# controller.net
KiCad netlist of a schematic drawn in EAGLE
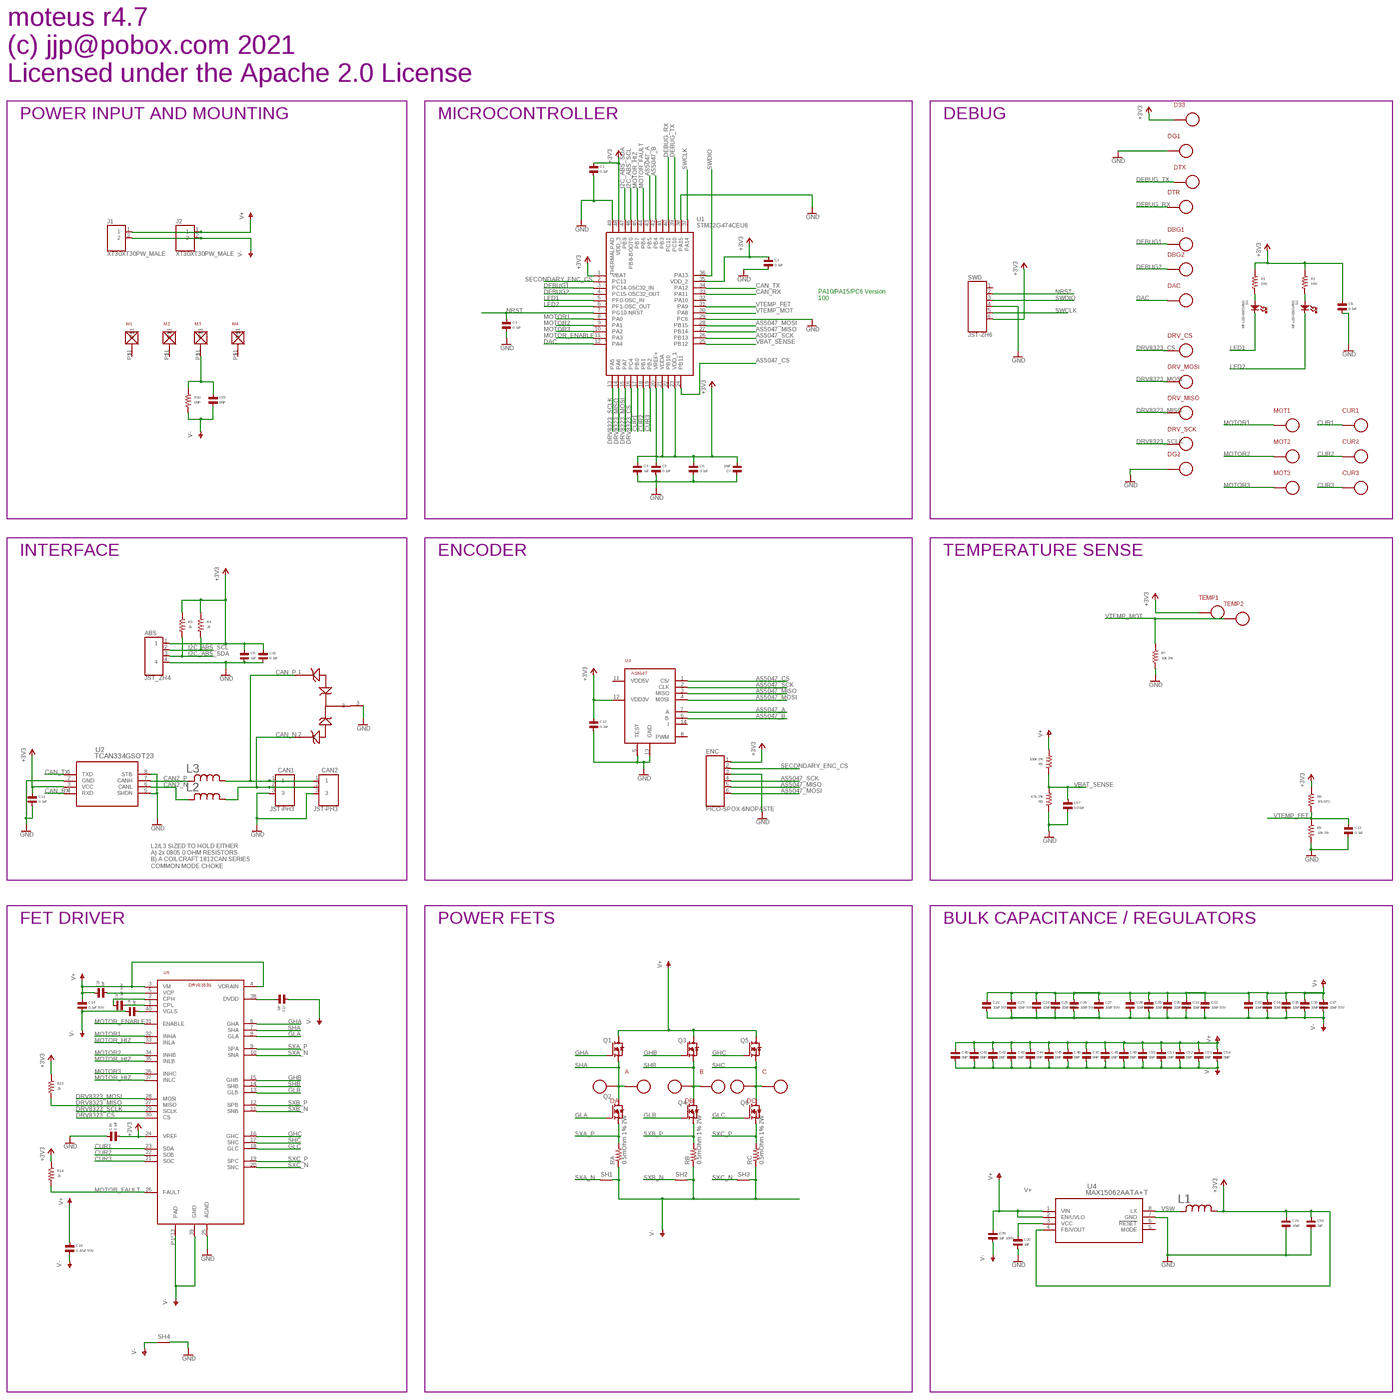
[diagram p0: schematic, sheet 1, overview]
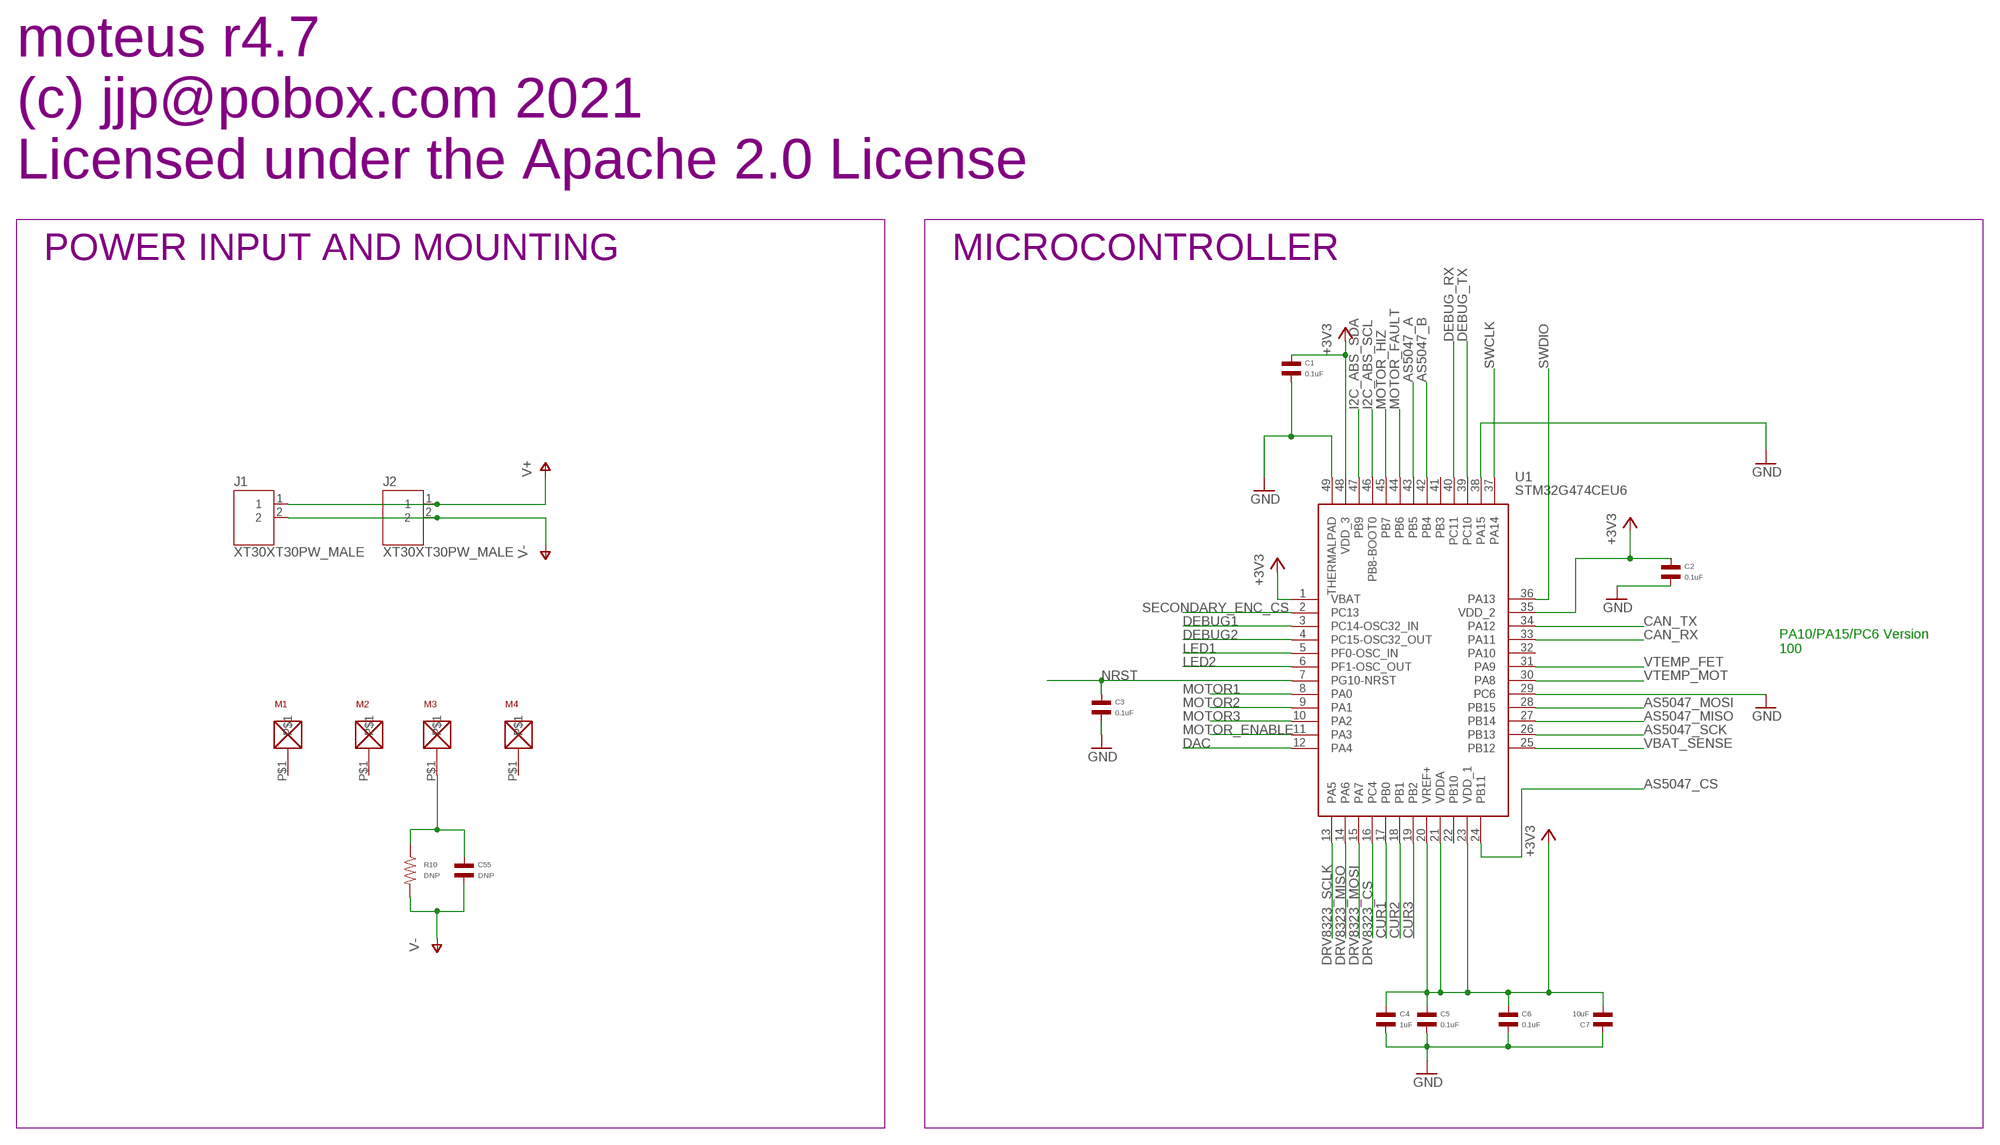
[diagram p1: schematic, sheet 1, part 1 of 4]
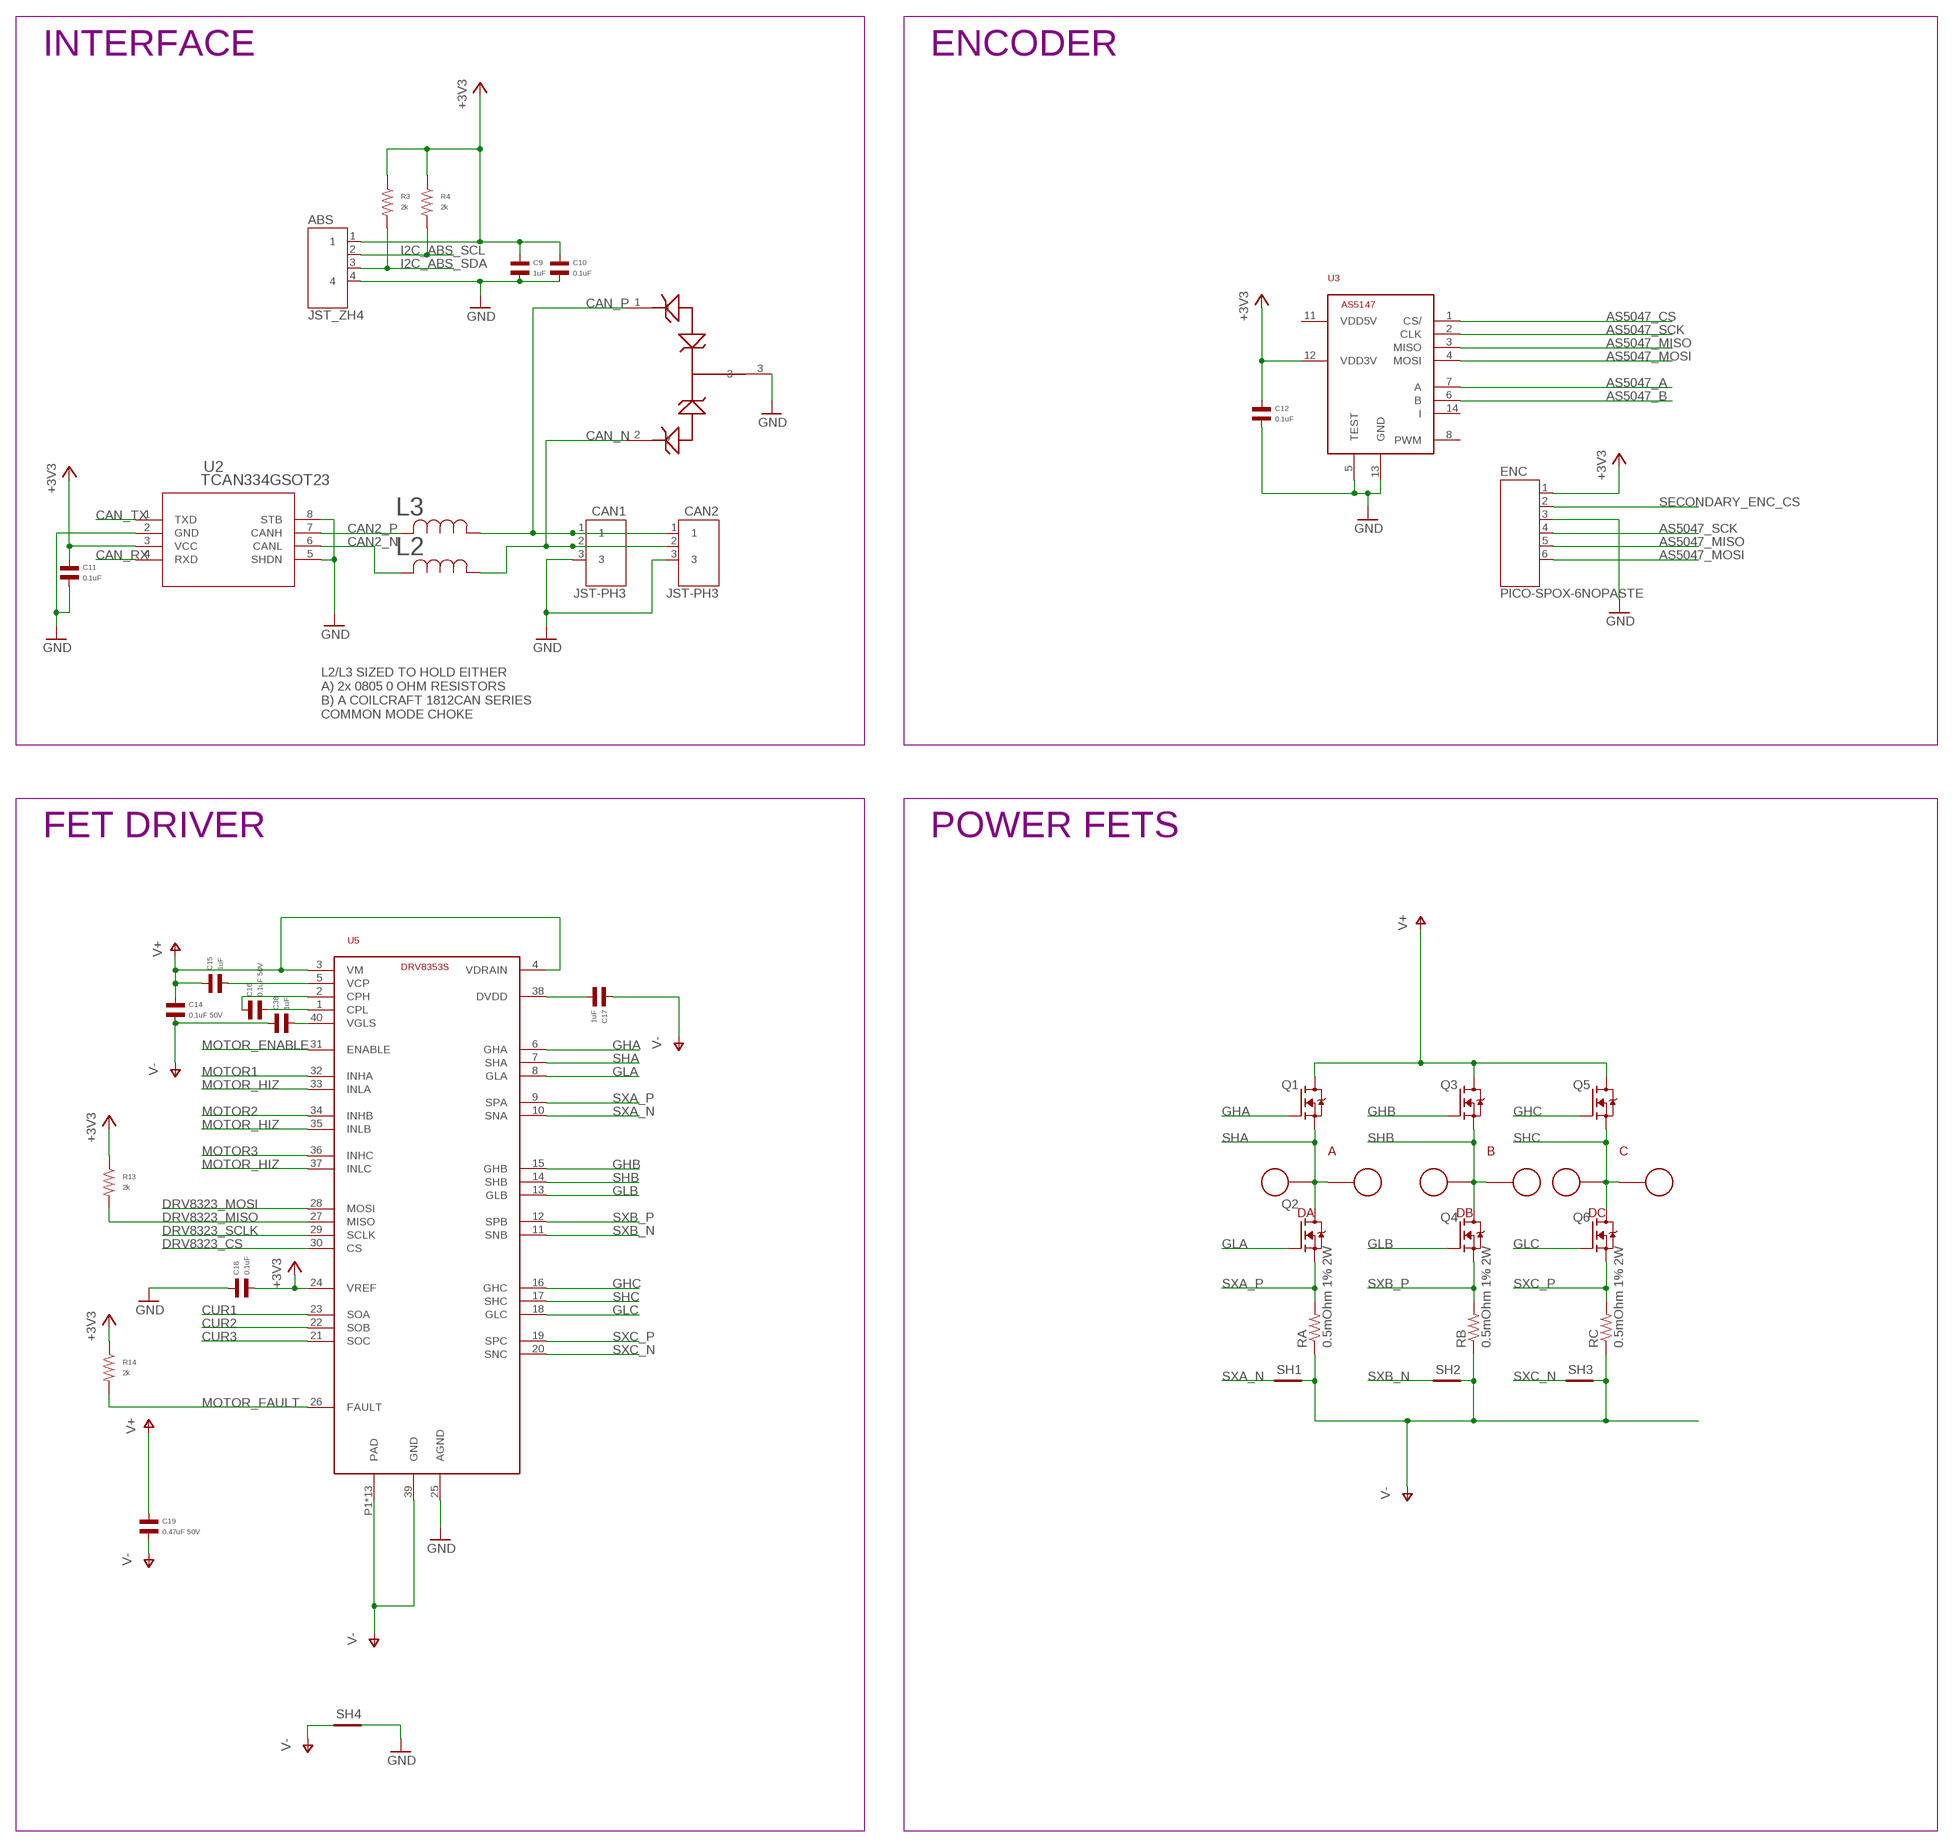
[diagram p2: schematic, sheet 1, part 2 of 4]
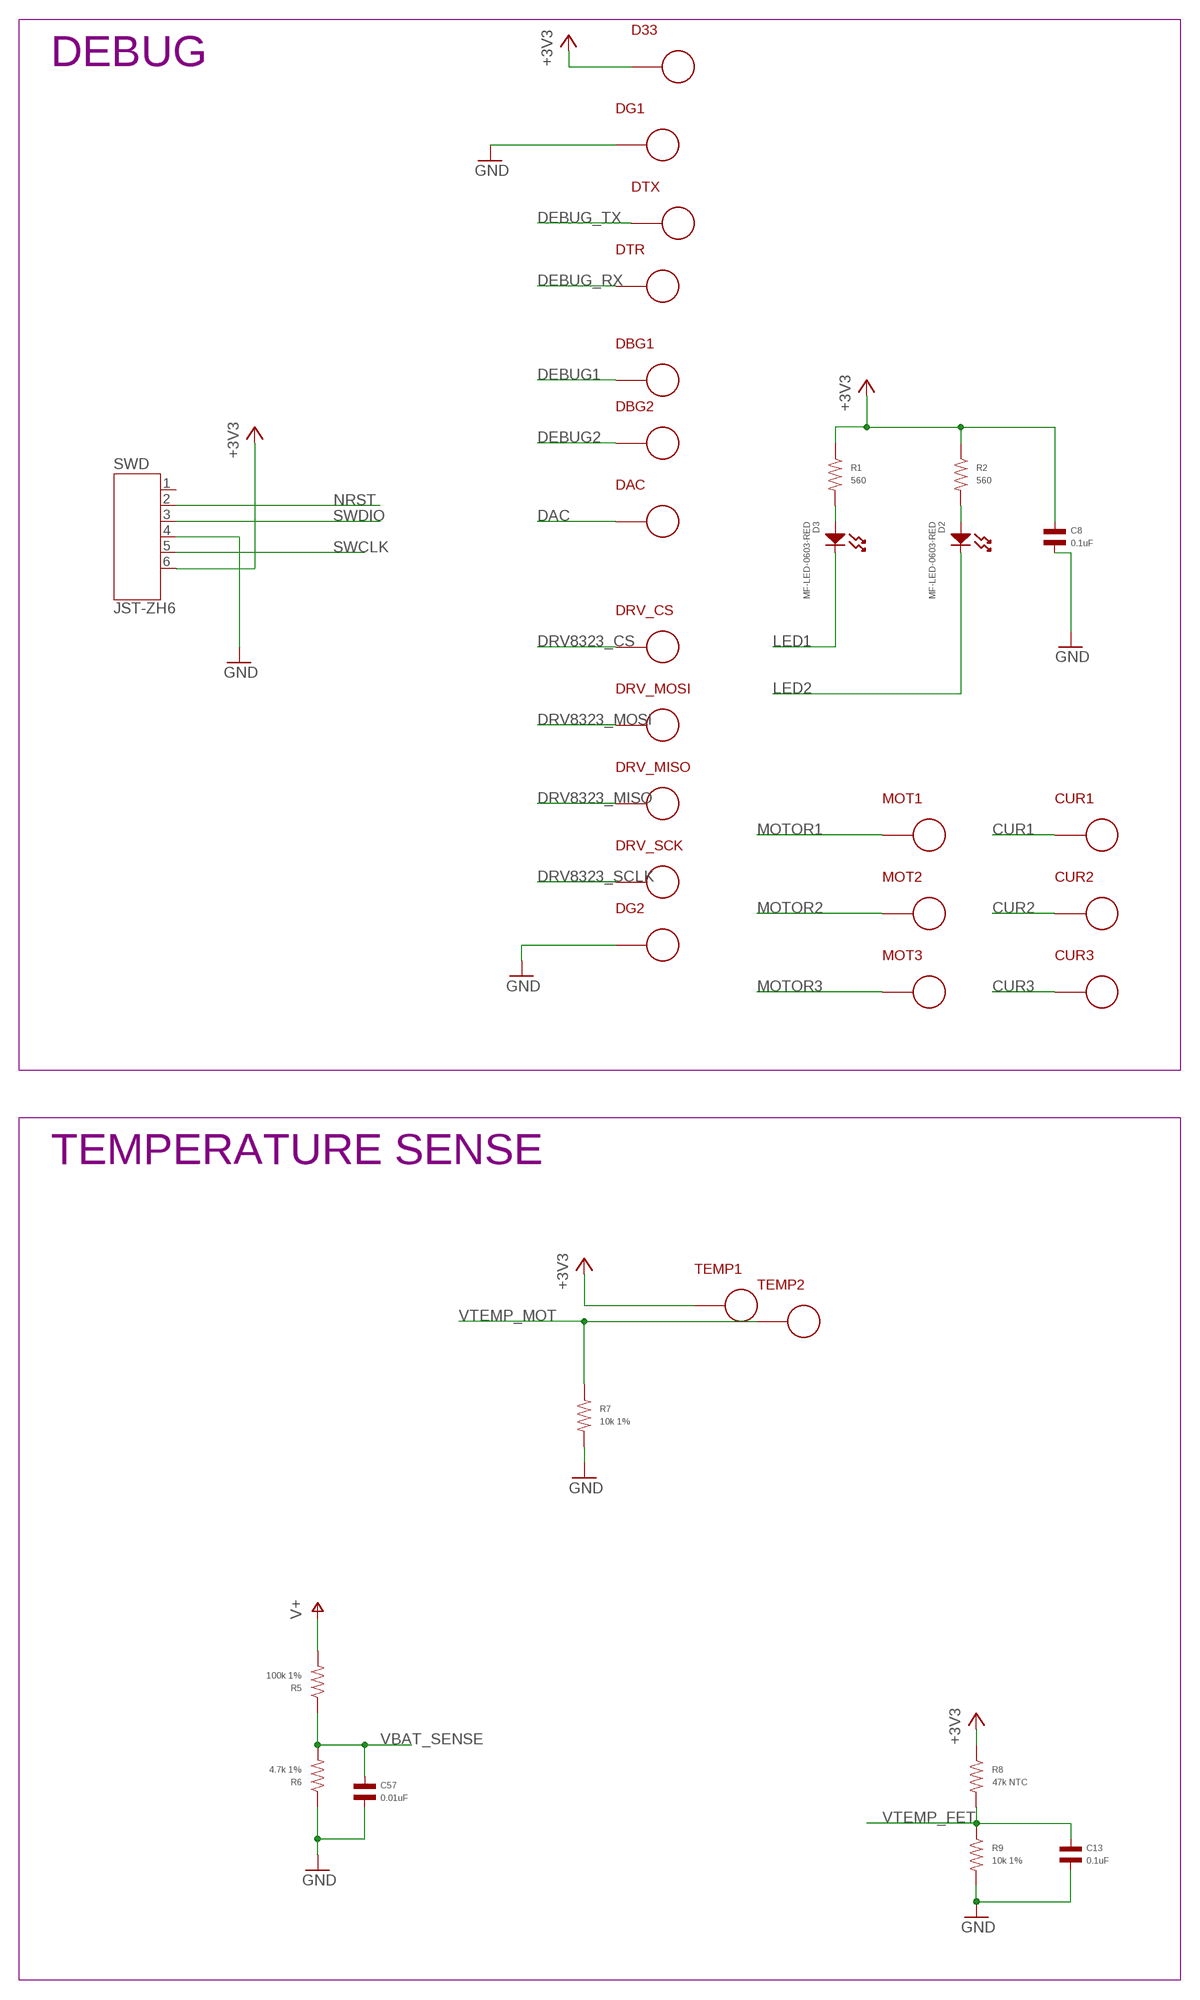
[diagram p3: schematic, sheet 1, part 3 of 4]
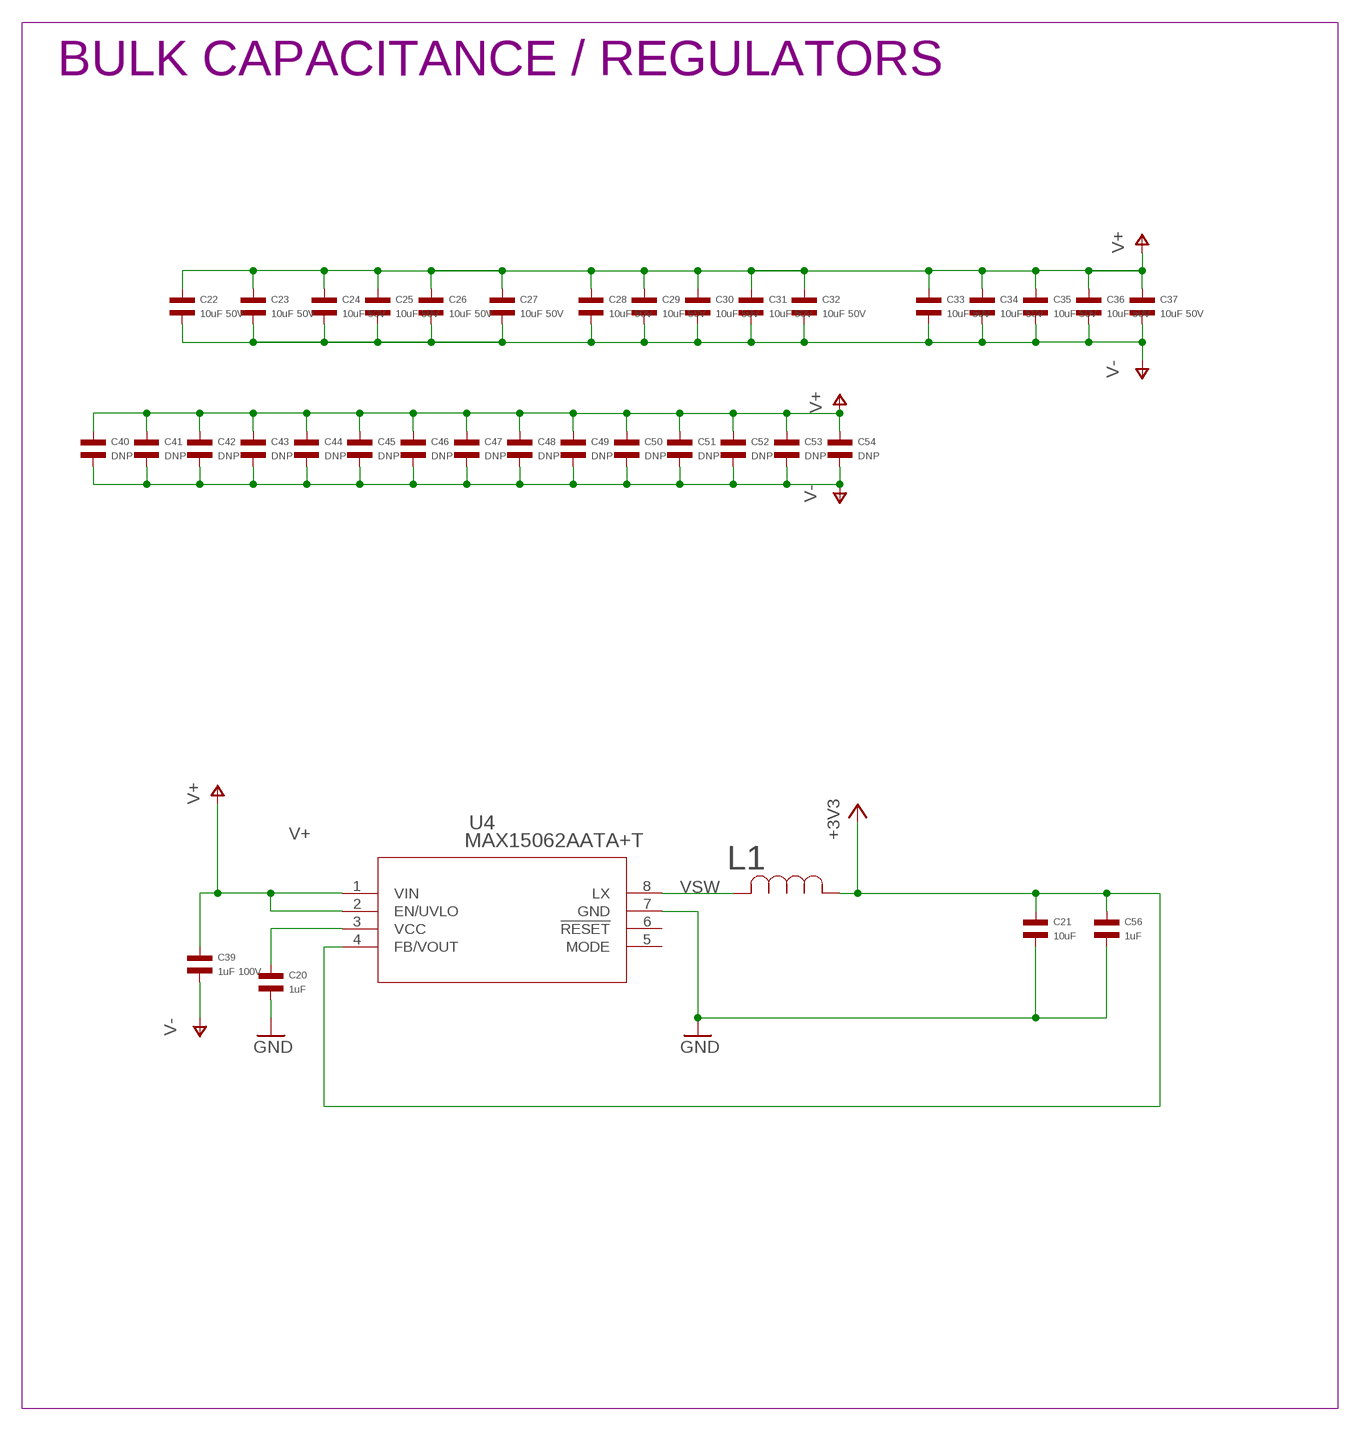
[diagram p4: schematic, sheet 1, part 4 of 4]

(export (version "E")
  (design (tool "Eeschema 10.0.6"))
  (components
    (comp (ref "A")
      (value "PAD16AWG_PAD")
      (footprint "eagle-import:16AWG_PAD")
      (libsource (lib "eagle-import") (part "PAD16AWG_PAD"))
    )
    (comp (ref "ABS")
      (value "JST_ZH4")
      (footprint "eagle-import:JST_S4B-ZR-SM4A-TF(LF)(SN)")
      (fields (field (name "MF") "JST") (field (name "MPN") "S4B-ZR-SM4A-TF(LF)(SN)"))
      (libsource (lib "eagle-import") (part "JST_ZH4"))
    )
    (comp (ref "B")
      (value "PAD16AWG_PAD")
      (footprint "eagle-import:16AWG_PAD")
      (libsource (lib "eagle-import") (part "PAD16AWG_PAD"))
    )
    (comp (ref "C")
      (value "PAD16AWG_PAD")
      (footprint "eagle-import:16AWG_PAD")
      (libsource (lib "eagle-import") (part "PAD16AWG_PAD"))
    )
    (comp (ref "C1")
      (value "0.1uF")
      (footprint "eagle-import:C0402")
      (fields (field (name "HOUSEPART") "YES") (field (name "MPN") "MF-CAP-0402-0.1uF"))
      (libsource (lib "eagle-import") (part "mfpassives_CAPACITOR_NP_0402"))
    )
    (comp (ref "C2")
      (value "0.1uF")
      (footprint "eagle-import:C0402")
      (fields (field (name "HOUSEPART") "YES") (field (name "MPN") "MF-CAP-0402-0.1uF"))
      (libsource (lib "eagle-import") (part "mfpassives_CAPACITOR_NP_0402"))
    )
    (comp (ref "C3")
      (value "0.1uF")
      (footprint "eagle-import:C0402")
      (fields (field (name "HOUSEPART") "YES") (field (name "MPN") "MF-CAP-0402-0.1uF"))
      (libsource (lib "eagle-import") (part "mfpassives_CAPACITOR_NP_0402"))
    )
    (comp (ref "C4")
      (value "1uF")
      (footprint "eagle-import:C0402")
      (fields (field (name "HOUSEPART") "YES") (field (name "MPN") "MF-CAP-0402-1uF"))
      (libsource (lib "eagle-import") (part "mfpassives_CAPACITOR_NP_0402"))
    )
    (comp (ref "C5")
      (value "0.1uF")
      (footprint "eagle-import:C0402")
      (fields (field (name "HOUSEPART") "YES") (field (name "MPN") "MF-CAP-0402-0.1uF"))
      (libsource (lib "eagle-import") (part "mfpassives_CAPACITOR_NP_0402"))
    )
    (comp (ref "C6")
      (value "0.1uF")
      (footprint "eagle-import:C0402")
      (fields (field (name "HOUSEPART") "YES") (field (name "MPN") "MF-CAP-0402-0.1uF"))
      (libsource (lib "eagle-import") (part "mfpassives_CAPACITOR_NP_0402"))
    )
    (comp (ref "C7")
      (value "10uF")
      (footprint "eagle-import:C1206")
      (fields (field (name "HOUSEPART") "YES") (field (name "MPN") "MF-CAP-1206-10uF"))
      (libsource (lib "eagle-import") (part "mfpassives_CAPACITOR_NP_1206"))
    )
    (comp (ref "C8")
      (value "0.1uF")
      (footprint "eagle-import:C0402")
      (fields (field (name "HOUSEPART") "YES") (field (name "MPN") "MF-CAP-0402-0.1uF"))
      (libsource (lib "eagle-import") (part "mfpassives_CAPACITOR_NP_0402"))
    )
    (comp (ref "C9")
      (value "1uF")
      (footprint "eagle-import:C0402")
      (fields (field (name "HOUSEPART") "YES") (field (name "MPN") "MF-CAP-0402-1uF"))
      (libsource (lib "eagle-import") (part "mfpassives_CAPACITOR_NP_0402"))
    )
    (comp (ref "C10")
      (value "0.1uF")
      (footprint "eagle-import:C0402")
      (fields (field (name "HOUSEPART") "YES") (field (name "MPN") "MF-CAP-0402-0.1uF"))
      (libsource (lib "eagle-import") (part "mfpassives_CAPACITOR_NP_0402"))
    )
    (comp (ref "C11")
      (value "0.1uF")
      (footprint "eagle-import:C0402")
      (fields (field (name "HOUSEPART") "YES") (field (name "MPN") "MF-CAP-0402-0.1uF"))
      (libsource (lib "eagle-import") (part "mfpassives_CAPACITOR_NP_0402"))
    )
    (comp (ref "C12")
      (value "0.1uF")
      (footprint "eagle-import:C0402")
      (fields (field (name "HOUSEPART") "YES") (field (name "MPN") "MF-CAP-0402-0.1uF"))
      (libsource (lib "eagle-import") (part "mfpassives_CAPACITOR_NP_0402"))
    )
    (comp (ref "C13")
      (value "0.1uF")
      (footprint "eagle-import:C0402")
      (fields (field (name "HOUSEPART") "YES") (field (name "MPN") "MF-CAP-0402-0.1uF"))
      (libsource (lib "eagle-import") (part "mfpassives_CAPACITOR_NP_0402"))
    )
    (comp (ref "C14")
      (value "0.1uF 50V")
      (footprint "eagle-import:C0402")
      (fields (field (name "MF") "TDK") (field (name "MPN") "CGA2B3X7R1H104K050BB"))
      (libsource (lib "eagle-import") (part "mfpassives_CAPACITOR_NP_0402"))
    )
    (comp (ref "C15")
      (value "1uF")
      (footprint "eagle-import:C0402")
      (fields (field (name "HOUSEPART") "YES") (field (name "MPN") "MF-CAP-0402-1uF"))
      (libsource (lib "eagle-import") (part "mfpassives_CAPACITOR_NP_0402"))
    )
    (comp (ref "C16")
      (value "0.1uF 50V")
      (footprint "eagle-import:C0402")
      (fields (field (name "MF") "TDK") (field (name "MPN") "CGA2B3X7R1H104K050BB"))
      (libsource (lib "eagle-import") (part "mfpassives_CAPACITOR_NP_0402"))
    )
    (comp (ref "C17")
      (value "1uF")
      (footprint "eagle-import:C0402")
      (fields (field (name "HOUSEPART") "YES") (field (name "MPN") "MF-CAP-0402-1uF"))
      (libsource (lib "eagle-import") (part "mfpassives_CAPACITOR_NP_0402"))
    )
    (comp (ref "C18")
      (value "0.1uF")
      (footprint "eagle-import:C0402")
      (fields (field (name "HOUSEPART") "YES") (field (name "MPN") "MF-CAP-0402-0.1uF"))
      (libsource (lib "eagle-import") (part "mfpassives_CAPACITOR_NP_0402"))
    )
    (comp (ref "C19")
      (value "0.47uF 50V")
      (footprint "eagle-import:C0402")
      (fields (field (name "MF") "Murata") (field (name "MPN") "GRM155R61H474KE11D"))
      (libsource (lib "eagle-import") (part "mfpassives_CAPACITOR_NP_0402"))
    )
    (comp (ref "C20")
      (value "1uF")
      (footprint "eagle-import:C0603")
      (fields (field (name "HOUSEPART") "1") (field (name "MPN") "MF-CAP-0603-1uF"))
      (libsource (lib "eagle-import") (part "mfpassives_CAPACITOR_NP_0603"))
    )
    (comp (ref "C21")
      (value "10uF")
      (footprint "eagle-import:C1206")
      (fields (field (name "HOUSEPART") "1") (field (name "MPN") "MF-CAP-1206-10uF"))
      (libsource (lib "eagle-import") (part "mfpassives_CAPACITOR_NP_1206"))
    )
    (comp (ref "C22")
      (value "10uF 50V")
      (footprint "eagle-import:C1206")
      (fields (field (name "MF") "TDK") (field (name "MPN") "C3216X7R1H106K160AE"))
      (libsource (lib "eagle-import") (part "mfpassives_CAPACITOR_NP_1206"))
    )
    (comp (ref "C23")
      (value "10uF 50V")
      (footprint "eagle-import:C1206")
      (fields (field (name "MF") "TDK") (field (name "MPN") "C3216X7R1H106K160AE"))
      (libsource (lib "eagle-import") (part "mfpassives_CAPACITOR_NP_1206"))
    )
    (comp (ref "C24")
      (value "10uF 50V")
      (footprint "eagle-import:C1206")
      (fields (field (name "MF") "TDK") (field (name "MPN") "C3216X7R1H106K160AE"))
      (libsource (lib "eagle-import") (part "mfpassives_CAPACITOR_NP_1206"))
    )
    (comp (ref "C25")
      (value "10uF 50V")
      (footprint "eagle-import:C1206")
      (fields (field (name "MF") "TDK") (field (name "MPN") "C3216X7R1H106K160AE"))
      (libsource (lib "eagle-import") (part "mfpassives_CAPACITOR_NP_1206"))
    )
    (comp (ref "C26")
      (value "10uF 50V")
      (footprint "eagle-import:C1206")
      (fields (field (name "MF") "TDK") (field (name "MPN") "C3216X7R1H106K160AE"))
      (libsource (lib "eagle-import") (part "mfpassives_CAPACITOR_NP_1206"))
    )
    (comp (ref "C27")
      (value "10uF 50V")
      (footprint "eagle-import:C1206")
      (fields (field (name "MF") "TDK") (field (name "MPN") "C3216X7R1H106K160AE"))
      (libsource (lib "eagle-import") (part "mfpassives_CAPACITOR_NP_1206"))
    )
    (comp (ref "C28")
      (value "10uF 50V")
      (footprint "eagle-import:C1206")
      (fields (field (name "MF") "TDK") (field (name "MPN") "C3216X7R1H106K160AE"))
      (libsource (lib "eagle-import") (part "mfpassives_CAPACITOR_NP_1206"))
    )
    (comp (ref "C29")
      (value "10uF 50V")
      (footprint "eagle-import:C1206")
      (fields (field (name "MF") "TDK") (field (name "MPN") "C3216X7R1H106K160AE"))
      (libsource (lib "eagle-import") (part "mfpassives_CAPACITOR_NP_1206"))
    )
    (comp (ref "C30")
      (value "10uF 50V")
      (footprint "eagle-import:C1206")
      (fields (field (name "MF") "TDK") (field (name "MPN") "C3216X7R1H106K160AE"))
      (libsource (lib "eagle-import") (part "mfpassives_CAPACITOR_NP_1206"))
    )
    (comp (ref "C31")
      (value "10uF 50V")
      (footprint "eagle-import:C1206")
      (fields (field (name "MF") "TDK") (field (name "MPN") "C3216X7R1H106K160AE"))
      (libsource (lib "eagle-import") (part "mfpassives_CAPACITOR_NP_1206"))
    )
    (comp (ref "C32")
      (value "10uF 50V")
      (footprint "eagle-import:C1206")
      (fields (field (name "MF") "TDK") (field (name "MPN") "C3216X7R1H106K160AE"))
      (libsource (lib "eagle-import") (part "mfpassives_CAPACITOR_NP_1206"))
    )
    (comp (ref "C33")
      (value "10uF 50V")
      (footprint "eagle-import:C1206")
      (fields (field (name "MF") "TDK") (field (name "MPN") "C3216X7R1H106K160AE"))
      (libsource (lib "eagle-import") (part "mfpassives_CAPACITOR_NP_1206"))
    )
    (comp (ref "C34")
      (value "10uF 50V")
      (footprint "eagle-import:C1206")
      (fields (field (name "MF") "TDK") (field (name "MPN") "C3216X7R1H106K160AE"))
      (libsource (lib "eagle-import") (part "mfpassives_CAPACITOR_NP_1206"))
    )
    (comp (ref "C35")
      (value "10uF 50V")
      (footprint "eagle-import:C1206")
      (fields (field (name "MF") "TDK") (field (name "MPN") "C3216X7R1H106K160AE"))
      (libsource (lib "eagle-import") (part "mfpassives_CAPACITOR_NP_1206"))
    )
    (comp (ref "C36")
      (value "10uF 50V")
      (footprint "eagle-import:C1206")
      (fields (field (name "MF") "TDK") (field (name "MPN") "C3216X7R1H106K160AE"))
      (libsource (lib "eagle-import") (part "mfpassives_CAPACITOR_NP_1206"))
    )
    (comp (ref "C37")
      (value "10uF 50V")
      (footprint "eagle-import:C1206")
      (fields (field (name "MF") "TDK") (field (name "MPN") "C3216X7R1H106K160AE"))
      (libsource (lib "eagle-import") (part "mfpassives_CAPACITOR_NP_1206"))
    )
    (comp (ref "C38")
      (value "1uF")
      (footprint "eagle-import:C0402")
      (fields (field (name "HOUSEPART") "YES") (field (name "MPN") "MF-CAP-0402-1uF"))
      (libsource (lib "eagle-import") (part "mfpassives_CAPACITOR_NP_0402"))
    )
    (comp (ref "C39")
      (value "1uF 100V")
      (footprint "eagle-import:C0805")
      (fields (field (name "MF") "MURATA") (field (name "MPN") "GCM21BC72A105KE36L"))
      (libsource (lib "eagle-import") (part "mfpassives_CAPACITOR_NP_0805"))
    )
    (comp (ref "C40")
      (value "DNP")
      (footprint "eagle-import:C1206_NOCREAM")
      (libsource (lib "eagle-import") (part "CAPACITOR_NP_1206_NOCREAM"))
    )
    (comp (ref "C41")
      (value "DNP")
      (footprint "eagle-import:C1206_NOCREAM")
      (libsource (lib "eagle-import") (part "CAPACITOR_NP_1206_NOCREAM"))
    )
    (comp (ref "C42")
      (value "DNP")
      (footprint "eagle-import:C1206_NOCREAM")
      (libsource (lib "eagle-import") (part "CAPACITOR_NP_1206_NOCREAM"))
    )
    (comp (ref "C43")
      (value "DNP")
      (footprint "eagle-import:C1206_NOCREAM")
      (libsource (lib "eagle-import") (part "CAPACITOR_NP_1206_NOCREAM"))
    )
    (comp (ref "C44")
      (value "DNP")
      (footprint "eagle-import:C1206_NOCREAM")
      (libsource (lib "eagle-import") (part "CAPACITOR_NP_1206_NOCREAM"))
    )
    (comp (ref "C45")
      (value "DNP")
      (footprint "eagle-import:C1206_NOCREAM")
      (libsource (lib "eagle-import") (part "CAPACITOR_NP_1206_NOCREAM"))
    )
    (comp (ref "C46")
      (value "DNP")
      (footprint "eagle-import:C1206_NOCREAM")
      (libsource (lib "eagle-import") (part "CAPACITOR_NP_1206_NOCREAM"))
    )
    (comp (ref "C47")
      (value "DNP")
      (footprint "eagle-import:C1206_NOCREAM")
      (libsource (lib "eagle-import") (part "CAPACITOR_NP_1206_NOCREAM"))
    )
    (comp (ref "C48")
      (value "DNP")
      (footprint "eagle-import:C1206_NOCREAM")
      (libsource (lib "eagle-import") (part "CAPACITOR_NP_1206_NOCREAM"))
    )
    (comp (ref "C49")
      (value "DNP")
      (footprint "eagle-import:C1206_NOCREAM")
      (libsource (lib "eagle-import") (part "CAPACITOR_NP_1206_NOCREAM"))
    )
    (comp (ref "C50")
      (value "DNP")
      (footprint "eagle-import:C1206_NOCREAM")
      (libsource (lib "eagle-import") (part "CAPACITOR_NP_1206_NOCREAM"))
    )
    (comp (ref "C51")
      (value "DNP")
      (footprint "eagle-import:C1206_NOCREAM")
      (libsource (lib "eagle-import") (part "CAPACITOR_NP_1206_NOCREAM"))
    )
    (comp (ref "C52")
      (value "DNP")
      (footprint "eagle-import:C1206_NOCREAM")
      (libsource (lib "eagle-import") (part "CAPACITOR_NP_1206_NOCREAM"))
    )
    (comp (ref "C53")
      (value "DNP")
      (footprint "eagle-import:C1206_NOCREAM")
      (libsource (lib "eagle-import") (part "CAPACITOR_NP_1206_NOCREAM"))
    )
    (comp (ref "C54")
      (value "DNP")
      (footprint "eagle-import:C1206_NOCREAM")
      (libsource (lib "eagle-import") (part "CAPACITOR_NP_1206_NOCREAM"))
    )
    (comp (ref "C55")
      (value "DNP")
      (footprint "eagle-import:C0402")
      (fields (field (name "POPULATE") "0"))
      (libsource (lib "eagle-import") (part "mfpassives_CAPACITOR_NP_0402"))
    )
    (comp (ref "C56")
      (value "1uF")
      (footprint "eagle-import:C0402")
      (fields (field (name "HOUSEPART") "YES") (field (name "MPN") "MF-CAP-0402-1uF"))
      (libsource (lib "eagle-import") (part "mfpassives_CAPACITOR_NP_0402"))
    )
    (comp (ref "C57")
      (value "0.01uF")
      (footprint "eagle-import:C0402")
      (fields (field (name "HOUSEPART") "YES") (field (name "MPN") "MF-CAP-0402-0.01uF"))
      (libsource (lib "eagle-import") (part "mfpassives_CAPACITOR_NP_0402"))
    )
    (comp (ref "CAN1")
      (value "JST-PH3")
      (footprint "eagle-import:JST_S3B-PH-SM4-TB(LF)(SN)")
      (fields (field (name "MF") "JST") (field (name "MPN") "S3B-PH-SM4-TB(LF)(SN)"))
      (libsource (lib "eagle-import") (part "JST-PH3"))
    )
    (comp (ref "CAN2")
      (value "JST-PH3")
      (footprint "eagle-import:JST_S3B-PH-SM4-TB(LF)(SN)")
      (fields (field (name "MF") "JST") (field (name "MPN") "S3B-PH-SM4-TB(LF)(SN)"))
      (libsource (lib "eagle-import") (part "JST-PH3"))
    )
    (comp (ref "CUR1")
      (value "PAD24AWG_PAD")
      (footprint "eagle-import:24AWG_PAD")
      (libsource (lib "eagle-import") (part "PAD24AWG_PAD"))
    )
    (comp (ref "CUR2")
      (value "PAD24AWG_PAD")
      (footprint "eagle-import:24AWG_PAD")
      (libsource (lib "eagle-import") (part "PAD24AWG_PAD"))
    )
    (comp (ref "CUR3")
      (value "PAD24AWG_PAD")
      (footprint "eagle-import:24AWG_PAD")
      (libsource (lib "eagle-import") (part "PAD24AWG_PAD"))
    )
    (comp (ref "D2")
      (value "MF-LED-0603-RED")
      (footprint "eagle-import:LED0603")
      (fields (field (name "HOUSEPART") "YES") (field (name "MPN") "MF-LED-0603-GREEN"))
      (libsource (lib "eagle-import") (part "LED_SINGLE-0603-RED"))
    )
    (comp (ref "D3")
      (value "MF-LED-0603-RED")
      (footprint "eagle-import:LED0603")
      (fields (field (name "HOUSEPART") "YES"))
      (libsource (lib "eagle-import") (part "LED_SINGLE-0603-RED"))
    )
    (comp (ref "D4")
      (value "DUAL_TVS")
      (footprint "eagle-import:SOT23-3")
      (fields (field (name "MPN") "CDSOT23-0502B"))
      (libsource (lib "eagle-import") (part "DUAL_TVS"))
    )
    (comp (ref "D33")
      (value "PAD24AWG_PAD")
      (footprint "eagle-import:24AWG_PAD")
      (libsource (lib "eagle-import") (part "PAD24AWG_PAD"))
    )
    (comp (ref "DA")
      (value "PAD24AWG_PAD")
      (footprint "eagle-import:24AWG_PAD")
      (libsource (lib "eagle-import") (part "PAD24AWG_PAD"))
    )
    (comp (ref "DAC")
      (value "PAD24AWG_PAD")
      (footprint "eagle-import:24AWG_PAD")
      (libsource (lib "eagle-import") (part "PAD24AWG_PAD"))
    )
    (comp (ref "DB")
      (value "PAD24AWG_PAD")
      (footprint "eagle-import:24AWG_PAD")
      (libsource (lib "eagle-import") (part "PAD24AWG_PAD"))
    )
    (comp (ref "DBG1")
      (value "PAD24AWG_PAD")
      (footprint "eagle-import:24AWG_PAD")
      (libsource (lib "eagle-import") (part "PAD24AWG_PAD"))
    )
    (comp (ref "DBG2")
      (value "PAD24AWG_PAD")
      (footprint "eagle-import:24AWG_PAD")
      (libsource (lib "eagle-import") (part "PAD24AWG_PAD"))
    )
    (comp (ref "DC")
      (value "PAD24AWG_PAD")
      (footprint "eagle-import:24AWG_PAD")
      (libsource (lib "eagle-import") (part "PAD24AWG_PAD"))
    )
    (comp (ref "DG1")
      (value "PAD24AWG_PAD")
      (footprint "eagle-import:24AWG_PAD")
      (libsource (lib "eagle-import") (part "PAD24AWG_PAD"))
    )
    (comp (ref "DG2")
      (value "PAD24AWG_PAD")
      (footprint "eagle-import:24AWG_PAD")
      (libsource (lib "eagle-import") (part "PAD24AWG_PAD"))
    )
    (comp (ref "DRV_CS")
      (value "PAD24AWG_PAD")
      (footprint "eagle-import:24AWG_PAD")
      (libsource (lib "eagle-import") (part "PAD24AWG_PAD"))
    )
    (comp (ref "DRV_MISO")
      (value "PAD24AWG_PAD")
      (footprint "eagle-import:24AWG_PAD")
      (libsource (lib "eagle-import") (part "PAD24AWG_PAD"))
    )
    (comp (ref "DRV_MOSI")
      (value "PAD24AWG_PAD")
      (footprint "eagle-import:24AWG_PAD")
      (libsource (lib "eagle-import") (part "PAD24AWG_PAD"))
    )
    (comp (ref "DRV_SCK")
      (value "PAD24AWG_PAD")
      (footprint "eagle-import:24AWG_PAD")
      (libsource (lib "eagle-import") (part "PAD24AWG_PAD"))
    )
    (comp (ref "DTR")
      (value "PAD24AWG_PAD")
      (footprint "eagle-import:24AWG_PAD")
      (libsource (lib "eagle-import") (part "PAD24AWG_PAD"))
    )
    (comp (ref "DTX")
      (value "PAD24AWG_PAD")
      (footprint "eagle-import:24AWG_PAD")
      (libsource (lib "eagle-import") (part "PAD24AWG_PAD"))
    )
    (comp (ref "ENC")
      (value "PICO-SPOX-6NOPASTE")
      (footprint "eagle-import:PICO-SPOX-SMT-RA-6-NOPASTE")
      (libsource (lib "eagle-import") (part "PICO-SPOX-6NOPASTE"))
    )
    (comp (ref "J1")
      (value "XT30XT30PW_MALE")
      (footprint "eagle-import:XT30PW_MALE")
      (libsource (lib "eagle-import") (part "XT30XT30PW_MALE"))
    )
    (comp (ref "J2")
      (value "XT30XT30PW_MALE")
      (footprint "eagle-import:XT30PW_MALE")
      (libsource (lib "eagle-import") (part "XT30XT30PW_MALE"))
    )
    (comp (ref "L1")
      (value "SRN4018-220M")
      (footprint "eagle-import:IND_BOURNS_SRN4018")
      (fields
        (field (name "MANUFACTURER_PART_NUMBER") "SRN4018220M")
        (field (name "MANUFACTURER_PART_NUMBER_1") "SRN4018-330M")
        (field (name "MPN") "SRN4018-330M")
      )
      (libsource (lib "eagle-import") (part "SRN4018-220M"))
    )
    (comp (ref "L2")
      (value "HALF_CHOKE")
      (footprint "eagle-import:1812_COMMON_HALF")
      (fields (field (name "MPN") "MF-RES-0805-0"))
      (libsource (lib "eagle-import") (part "HALF_CHOKE"))
    )
    (comp (ref "L3")
      (value "HALF_CHOKE")
      (footprint "eagle-import:1812_COMMON_HALF")
      (fields (field (name "MPN") "MF-RES-0805-0"))
      (libsource (lib "eagle-import") (part "HALF_CHOKE"))
    )
    (comp (ref "M1")
      (value "MOUNT")
      (footprint "eagle-import:M2.5MOUNT")
      (libsource (lib "eagle-import") (part "MOUNT"))
    )
    (comp (ref "M2")
      (value "MOUNT")
      (footprint "eagle-import:M2.5MOUNT")
      (libsource (lib "eagle-import") (part "MOUNT"))
    )
    (comp (ref "M3")
      (value "MOUNT")
      (footprint "eagle-import:M2.5MOUNT")
      (libsource (lib "eagle-import") (part "MOUNT"))
    )
    (comp (ref "M4")
      (value "MOUNT")
      (footprint "eagle-import:M2.5MOUNT")
      (libsource (lib "eagle-import") (part "MOUNT"))
    )
    (comp (ref "MOT1")
      (value "PAD24AWG_PAD")
      (footprint "eagle-import:24AWG_PAD")
      (libsource (lib "eagle-import") (part "PAD24AWG_PAD"))
    )
    (comp (ref "MOT2")
      (value "PAD24AWG_PAD")
      (footprint "eagle-import:24AWG_PAD")
      (libsource (lib "eagle-import") (part "PAD24AWG_PAD"))
    )
    (comp (ref "MOT3")
      (value "PAD24AWG_PAD")
      (footprint "eagle-import:24AWG_PAD")
      (libsource (lib "eagle-import") (part "PAD24AWG_PAD"))
    )
    (comp (ref "Q1")
      (value "TPH1R204PLSOP_ADVANCE_8")
      (footprint "eagle-import:SOP_ADVANCE_8")
      (fields
        (field (name "MF") "Toshiba")
        (field (name "MPN") "TPH1R204PL")
        (field (name "MF_1") "Toshiba")
        (field (name "MPN_1") "TPH2R506PL,L1Q")
      )
      (libsource (lib "eagle-import") (part "TPH1R204PLSOP_ADVANCE_8"))
    )
    (comp (ref "Q2")
      (value "TPH1R204PLSOP_ADVANCE_8")
      (footprint "eagle-import:SOP_ADVANCE_8")
      (fields
        (field (name "MF") "Toshiba")
        (field (name "MPN") "TPH1R204PL")
        (field (name "MF_1") "Toshiba")
        (field (name "MPN_1") "TPH2R506PL,L1Q")
      )
      (libsource (lib "eagle-import") (part "TPH1R204PLSOP_ADVANCE_8"))
    )
    (comp (ref "Q3")
      (value "TPH1R204PLSOP_ADVANCE_8")
      (footprint "eagle-import:SOP_ADVANCE_8")
      (fields
        (field (name "MF") "Toshiba")
        (field (name "MPN") "TPH1R204PL")
        (field (name "MF_1") "Toshiba")
        (field (name "MPN_1") "TPH2R506PL,L1Q")
      )
      (libsource (lib "eagle-import") (part "TPH1R204PLSOP_ADVANCE_8"))
    )
    (comp (ref "Q4")
      (value "TPH1R204PLSOP_ADVANCE_8")
      (footprint "eagle-import:SOP_ADVANCE_8")
      (fields
        (field (name "MF") "Toshiba")
        (field (name "MPN") "TPH1R204PL")
        (field (name "MF_1") "Toshiba")
        (field (name "MPN_1") "TPH2R506PL,L1Q")
      )
      (libsource (lib "eagle-import") (part "TPH1R204PLSOP_ADVANCE_8"))
    )
    (comp (ref "Q5")
      (value "TPH1R204PLSOP_ADVANCE_8")
      (footprint "eagle-import:SOP_ADVANCE_8")
      (fields
        (field (name "MF") "Toshiba")
        (field (name "MPN") "TPH1R204PL")
        (field (name "MF_1") "Toshiba")
        (field (name "MPN_1") "TPH2R506PL,L1Q")
      )
      (libsource (lib "eagle-import") (part "TPH1R204PLSOP_ADVANCE_8"))
    )
    (comp (ref "Q6")
      (value "TPH1R204PLSOP_ADVANCE_8")
      (footprint "eagle-import:SOP_ADVANCE_8")
      (fields
        (field (name "MF") "Toshiba")
        (field (name "MPN") "TPH1R204PL")
        (field (name "MF_1") "Toshiba")
        (field (name "MPN_1") "TPH2R506PL,L1Q")
      )
      (libsource (lib "eagle-import") (part "TPH1R204PLSOP_ADVANCE_8"))
    )
    (comp (ref "R1")
      (value "560")
      (footprint "eagle-import:R0402")
      (fields (field (name "HOUSEPART") "1") (field (name "MPN") "MF-RES-0402-560"))
      (libsource (lib "eagle-import") (part "RESISTOR_0402"))
    )
    (comp (ref "R2")
      (value "560")
      (footprint "eagle-import:R0402")
      (fields (field (name "HOUSEPART") "1") (field (name "MPN") "MF-RES-0402-560"))
      (libsource (lib "eagle-import") (part "RESISTOR_0402"))
    )
    (comp (ref "R3")
      (value "2k")
      (footprint "eagle-import:R0402")
      (fields (field (name "HOUSEPART") "YES") (field (name "MPN") "MF-RES-0402-2K"))
      (libsource (lib "eagle-import") (part "RESISTOR_0402"))
    )
    (comp (ref "R4")
      (value "2k")
      (footprint "eagle-import:R0402")
      (fields (field (name "HOUSEPART") "YES") (field (name "MPN") "MF-RES-0402-2K"))
      (libsource (lib "eagle-import") (part "RESISTOR_0402"))
    )
    (comp (ref "R5")
      (value "100k 1%")
      (footprint "eagle-import:R0402")
      (fields (field (name "MF") "Yageo") (field (name "MPN") "RC0402FR-07100KL"))
      (libsource (lib "eagle-import") (part "RESISTOR_0402"))
    )
    (comp (ref "R6")
      (value "4.7k 1%")
      (footprint "eagle-import:R0402")
      (fields (field (name "MF") "Yageo") (field (name "MPN") "RC0402FR-074K7L"))
      (libsource (lib "eagle-import") (part "RESISTOR_0402"))
    )
    (comp (ref "R7")
      (value "10k 1%")
      (footprint "eagle-import:R0402")
      (fields (field (name "MF") "Yageo") (field (name "MPN") "RC0402FR-0710KL"))
      (libsource (lib "eagle-import") (part "RESISTOR_0402"))
    )
    (comp (ref "R8")
      (value "47k NTC")
      (footprint "eagle-import:R0402")
      (fields (field (name "MF") "Murata") (field (name "MPN") "NCP15WB473F03RC"))
      (libsource (lib "eagle-import") (part "RESISTOR_0402"))
    )
    (comp (ref "R9")
      (value "10k 1%")
      (footprint "eagle-import:R0402")
      (fields (field (name "MF") "Yageo") (field (name "MPN") "RC0402FR-0710KL"))
      (libsource (lib "eagle-import") (part "RESISTOR_0402"))
    )
    (comp (ref "R10")
      (value "DNP")
      (footprint "eagle-import:R0402")
      (fields (field (name "POPULATE") "0"))
      (libsource (lib "eagle-import") (part "RESISTOR_0402"))
    )
    (comp (ref "R13")
      (value "2k")
      (footprint "eagle-import:R0402")
      (fields (field (name "HOUSEPART") "YES") (field (name "MPN") "MF-RES-0402-2K"))
      (libsource (lib "eagle-import") (part "RESISTOR_0402"))
    )
    (comp (ref "R14")
      (value "2k")
      (footprint "eagle-import:R0402")
      (fields (field (name "HOUSEPART") "YES") (field (name "MPN") "MF-RES-0402-2K"))
      (libsource (lib "eagle-import") (part "RESISTOR_0402"))
    )
    (comp (ref "RA")
      (value "0.5mOhm 1% 2W")
      (footprint "eagle-import:M1206")
      (fields (field (name "MF") "Stackpole Electronics") (field (name "MPN") "HCS1206FTL500"))
      (libsource (lib "eagle-import") (part "R-US_M1206"))
    )
    (comp (ref "RB")
      (value "0.5mOhm 1% 2W")
      (footprint "eagle-import:M1206")
      (fields (field (name "MF") "Stackpole Electronics") (field (name "MPN") "HCS1206FTL500"))
      (libsource (lib "eagle-import") (part "R-US_M1206"))
    )
    (comp (ref "RC")
      (value "0.5mOhm 1% 2W")
      (footprint "eagle-import:M1206")
      (fields (field (name "MF") "Stackpole Electronics") (field (name "MPN") "HCS1206FTL500"))
      (libsource (lib "eagle-import") (part "R-US_M1206"))
    )
    (comp (ref "SH1")
      (value "SHORTT5")
      (footprint "eagle-import:SHORT_TOP-50")
      (libsource (lib "eagle-import") (part "SHORTT5"))
    )
    (comp (ref "SH2")
      (value "SHORTT5")
      (footprint "eagle-import:SHORT_TOP-50")
      (libsource (lib "eagle-import") (part "SHORTT5"))
    )
    (comp (ref "SH3")
      (value "SHORTT5")
      (footprint "eagle-import:SHORT_TOP-50")
      (libsource (lib "eagle-import") (part "SHORTT5"))
    )
    (comp (ref "SH4")
      (value "SHORTMEDIUM")
      (footprint "eagle-import:SHORT_TOP-MEDIUM")
      (libsource (lib "eagle-import") (part "SHORTMEDIUM"))
    )
    (comp (ref "SWD")
      (value "JST-ZH6")
      (footprint "eagle-import:JST_S6B-ZR-SM4A-TF(LF)(SN)")
      (fields (field (name "MF") "JST") (field (name "MPN") "S6B-ZR-SM4A-TF(LF)(SN)"))
      (libsource (lib "eagle-import") (part "JST-ZH6"))
    )
    (comp (ref "TEMP1")
      (value "PAD24AWG_PAD")
      (footprint "eagle-import:24AWG_PAD")
      (libsource (lib "eagle-import") (part "PAD24AWG_PAD"))
    )
    (comp (ref "TEMP2")
      (value "PAD24AWG_PAD")
      (footprint "eagle-import:24AWG_PAD")
      (libsource (lib "eagle-import") (part "PAD24AWG_PAD"))
    )
    (comp (ref "U1")
      (value "STM32G474CEU6")
      (footprint "eagle-import:QFN50P700X700X60-49N")
      (fields (field (name "MOUSER_PART_NUMBER") "511-STM32G474CEU6"))
      (libsource (lib "eagle-import") (part "STM32G474CEU6"))
    )
    (comp (ref "U2")
      (value "TCAN334GSOT23")
      (footprint "eagle-import:SOT23-8")
      (fields (field (name "MF") "TI") (field (name "MPN") "TCAN334GDCNT"))
      (libsource (lib "eagle-import") (part "TCAN334GSOT23"))
    )
    (comp (ref "U3")
      (value "AS5147")
      (footprint "eagle-import:TSSOP14")
      (fields (field (name "MF") "AMS") (field (name "MPN") "AS5047P-ATSM"))
      (libsource (lib "eagle-import") (part "AS5147"))
    )
    (comp (ref "U4")
      (value "MAX15062AATA+T")
      (footprint "eagle-import:21-0487A_MXM")
      (fields (field (name "COPYRIGHT") "Copyright (C) 2018 Accelerated Designs. All rights reserved"))
      (libsource (lib "eagle-import") (part "MAX15062AATA+T"))
    )
    (comp (ref "U5")
      (value "DRV8353S")
      (footprint "eagle-import:WQFN-40")
      (fields (field (name "MF") "TI") (field (name "MPN") "DRV8353FSRTAR"))
      (libsource (lib "eagle-import") (part "DRV8353S"))
    )
  )
  (nets
    (net (code "1") (name "+3V3") (class "Default")
      (node (ref "ABS") (pin "1") (pinfunction "1_1") (pintype "passive"))
      (node (ref "C1") (pin "P$1") (pinfunction "P$1_P$1") (pintype "passive"))
      (node (ref "C10") (pin "P$1") (pinfunction "P$1_P$1") (pintype "passive"))
      (node (ref "C11") (pin "P$1") (pinfunction "P$1_P$1") (pintype "passive"))
      (node (ref "C12") (pin "P$1") (pinfunction "P$1_P$1") (pintype "passive"))
      (node (ref "C18") (pin "P$2") (pinfunction "P$2_P$2") (pintype "passive"))
      (node (ref "C2") (pin "P$1") (pinfunction "P$1_P$1") (pintype "passive"))
      (node (ref "C21") (pin "P$1") (pinfunction "P$1_P$1") (pintype "passive"))
      (node (ref "C4") (pin "P$1") (pinfunction "P$1_P$1") (pintype "passive"))
      (node (ref "C5") (pin "P$1") (pinfunction "P$1_P$1") (pintype "passive"))
      (node (ref "C56") (pin "P$1") (pinfunction "P$1_P$1") (pintype "passive"))
      (node (ref "C6") (pin "P$1") (pinfunction "P$1_P$1") (pintype "passive"))
      (node (ref "C7") (pin "P$2") (pinfunction "P$2_P$2") (pintype "passive"))
      (node (ref "C8") (pin "P$1") (pinfunction "P$1_P$1") (pintype "passive"))
      (node (ref "C9") (pin "P$1") (pinfunction "P$1_P$1") (pintype "passive"))
      (node (ref "D33") (pin "P$1") (pinfunction "P$1_P$1") (pintype "bidirectional"))
      (node (ref "ENC") (pin "1") (pinfunction "1_1") (pintype "passive"))
      (node (ref "L1") (pin "1") (pinfunction "1_1") (pintype "passive"))
      (node (ref "R1") (pin "P$1") (pinfunction "P$1_P$1") (pintype "passive"))
      (node (ref "R13") (pin "P$1") (pinfunction "P$1_P$1") (pintype "passive"))
      (node (ref "R14") (pin "P$1") (pinfunction "P$1_P$1") (pintype "passive"))
      (node (ref "R2") (pin "P$1") (pinfunction "P$1_P$1") (pintype "passive"))
      (node (ref "R3") (pin "P$1") (pinfunction "P$1_P$1") (pintype "passive"))
      (node (ref "R4") (pin "P$1") (pinfunction "P$1_P$1") (pintype "passive"))
      (node (ref "R8") (pin "P$1") (pinfunction "P$1_P$1") (pintype "passive"))
      (node (ref "SWD") (pin "6") (pinfunction "6_6") (pintype "passive"))
      (node (ref "TEMP1") (pin "P$1") (pinfunction "P$1_P$1") (pintype "bidirectional"))
      (node (ref "U1") (pin "1") (pinfunction "VBAT_1") (pintype "bidirectional"))
      (node (ref "U1") (pin "20") (pinfunction "VREF+_20") (pintype "bidirectional"))
      (node (ref "U1") (pin "21") (pinfunction "VDDA_21") (pintype "bidirectional"))
      (node (ref "U1") (pin "23") (pinfunction "VDD_1_23") (pintype "bidirectional"))
      (node (ref "U1") (pin "35") (pinfunction "VDD_2_35") (pintype "bidirectional"))
      (node (ref "U1") (pin "48") (pinfunction "VDD_3_48") (pintype "bidirectional"))
      (node (ref "U2") (pin "3") (pinfunction "VCC_3") (pintype "power_in"))
      (node (ref "U3") (pin "12") (pinfunction "VDD3V_12") (pintype "bidirectional"))
      (node (ref "U4") (pin "4") (pinfunction "FB/VOUT_4") (pintype "bidirectional"))
      (node (ref "U5") (pin "24") (pinfunction "VREF_24") (pintype "bidirectional"))
    )
    (net (code "2") (name "/AS5047_A") (class "Default")
      (node (ref "U1") (pin "43") (pinfunction "PB5_43") (pintype "bidirectional"))
      (node (ref "U3") (pin "7") (pinfunction "A_7") (pintype "bidirectional"))
    )
    (net (code "3") (name "/AS5047_B") (class "Default")
      (node (ref "U1") (pin "42") (pinfunction "PB4_42") (pintype "bidirectional"))
      (node (ref "U3") (pin "6") (pinfunction "B_6") (pintype "bidirectional"))
    )
    (net (code "4") (name "/AS5047_CS") (class "Default")
      (node (ref "U1") (pin "24") (pinfunction "PB11_24") (pintype "bidirectional"))
      (node (ref "U3") (pin "1") (pinfunction "CS/_1") (pintype "bidirectional"))
    )
    (net (code "5") (name "/AS5047_MISO") (class "Default")
      (node (ref "ENC") (pin "5") (pinfunction "5_5") (pintype "passive"))
      (node (ref "U1") (pin "27") (pinfunction "PB14_27") (pintype "bidirectional"))
      (node (ref "U3") (pin "3") (pinfunction "MISO_3") (pintype "bidirectional"))
    )
    (net (code "6") (name "/AS5047_MOSI") (class "Default")
      (node (ref "ENC") (pin "6") (pinfunction "6_6") (pintype "passive"))
      (node (ref "U1") (pin "28") (pinfunction "PB15_28") (pintype "bidirectional"))
      (node (ref "U3") (pin "4") (pinfunction "MOSI_4") (pintype "bidirectional"))
    )
    (net (code "7") (name "/AS5047_SCK") (class "Default")
      (node (ref "ENC") (pin "4") (pinfunction "4_4") (pintype "passive"))
      (node (ref "U1") (pin "26") (pinfunction "PB13_26") (pintype "bidirectional"))
      (node (ref "U3") (pin "2") (pinfunction "CLK_2") (pintype "bidirectional"))
    )
    (net (code "8") (name "/CAN2_N") (class "Default")
      (node (ref "L2") (pin "P$2") (pinfunction "2_P$2") (pintype "passive"))
      (node (ref "U2") (pin "6") (pinfunction "CANL_6") (pintype "bidirectional"))
    )
    (net (code "9") (name "/CAN2_P") (class "Default")
      (node (ref "L3") (pin "P$2") (pinfunction "2_P$2") (pintype "passive"))
      (node (ref "U2") (pin "7") (pinfunction "CANH_7") (pintype "bidirectional"))
    )
    (net (code "10") (name "/CAN_N") (class "Default")
      (node (ref "CAN1") (pin "2") (pinfunction "2_2") (pintype "passive"))
      (node (ref "CAN2") (pin "2") (pinfunction "2_2") (pintype "passive"))
      (node (ref "D4") (pin "2") (pinfunction "2_2") (pintype "bidirectional"))
      (node (ref "L2") (pin "P$1") (pinfunction "1_P$1") (pintype "passive"))
    )
    (net (code "11") (name "/CAN_P") (class "Default")
      (node (ref "CAN1") (pin "1") (pinfunction "1_1") (pintype "passive"))
      (node (ref "CAN2") (pin "1") (pinfunction "1_1") (pintype "passive"))
      (node (ref "D4") (pin "1") (pinfunction "1_1") (pintype "bidirectional"))
      (node (ref "L3") (pin "P$1") (pinfunction "1_P$1") (pintype "passive"))
    )
    (net (code "12") (name "/CAN_RX") (class "Default")
      (node (ref "U1") (pin "33") (pinfunction "PA11_33") (pintype "bidirectional"))
      (node (ref "U2") (pin "4") (pinfunction "RXD_4") (pintype "output"))
    )
    (net (code "13") (name "/CAN_TX") (class "Default")
      (node (ref "U1") (pin "34") (pinfunction "PA12_34") (pintype "bidirectional"))
      (node (ref "U2") (pin "1") (pinfunction "TXD_1") (pintype "input"))
    )
    (net (code "14") (name "/CUR1") (class "Default")
      (node (ref "CUR1") (pin "P$1") (pinfunction "P$1_P$1") (pintype "bidirectional"))
      (node (ref "U1") (pin "17") (pinfunction "PB0_17") (pintype "bidirectional"))
      (node (ref "U5") (pin "23") (pinfunction "SOA_23") (pintype "bidirectional"))
    )
    (net (code "15") (name "/CUR2") (class "Default")
      (node (ref "CUR2") (pin "P$1") (pinfunction "P$1_P$1") (pintype "bidirectional"))
      (node (ref "U1") (pin "18") (pinfunction "PB1_18") (pintype "bidirectional"))
      (node (ref "U5") (pin "22") (pinfunction "SOB_22") (pintype "bidirectional"))
    )
    (net (code "16") (name "/CUR3") (class "Default")
      (node (ref "CUR3") (pin "P$1") (pinfunction "P$1_P$1") (pintype "bidirectional"))
      (node (ref "U1") (pin "19") (pinfunction "PB2_19") (pintype "bidirectional"))
      (node (ref "U5") (pin "21") (pinfunction "SOC_21") (pintype "bidirectional"))
    )
    (net (code "17") (name "/DAC") (class "Default")
      (node (ref "DAC") (pin "P$1") (pinfunction "P$1_P$1") (pintype "bidirectional"))
      (node (ref "U1") (pin "12") (pinfunction "PA4_12") (pintype "bidirectional"))
    )
    (net (code "18") (name "/DEBUG1") (class "Default")
      (node (ref "DBG1") (pin "P$1") (pinfunction "P$1_P$1") (pintype "bidirectional"))
      (node (ref "U1") (pin "3") (pinfunction "PC14-OSC32_IN_3") (pintype "bidirectional"))
    )
    (net (code "19") (name "/DEBUG2") (class "Default")
      (node (ref "DBG2") (pin "P$1") (pinfunction "P$1_P$1") (pintype "bidirectional"))
      (node (ref "U1") (pin "4") (pinfunction "PC15-OSC32_OUT_4") (pintype "bidirectional"))
    )
    (net (code "20") (name "/DEBUG_RX") (class "Default")
      (node (ref "DTR") (pin "P$1") (pinfunction "P$1_P$1") (pintype "bidirectional"))
      (node (ref "U1") (pin "40") (pinfunction "PC11_40") (pintype "bidirectional"))
    )
    (net (code "21") (name "/DEBUG_TX") (class "Default")
      (node (ref "DTX") (pin "P$1") (pinfunction "P$1_P$1") (pintype "bidirectional"))
      (node (ref "U1") (pin "39") (pinfunction "PC10_39") (pintype "bidirectional"))
    )
    (net (code "22") (name "/DRV8323_CS") (class "Default")
      (node (ref "DRV_CS") (pin "P$1") (pinfunction "P$1_P$1") (pintype "bidirectional"))
      (node (ref "U1") (pin "16") (pinfunction "PC4_16") (pintype "bidirectional"))
      (node (ref "U5") (pin "30") (pinfunction "CS_30") (pintype "bidirectional"))
    )
    (net (code "23") (name "/DRV8323_MISO") (class "Default")
      (node (ref "DRV_MISO") (pin "P$1") (pinfunction "P$1_P$1") (pintype "bidirectional"))
      (node (ref "R13") (pin "P$2") (pinfunction "P$2_P$2") (pintype "passive"))
      (node (ref "U1") (pin "14") (pinfunction "PA6_14") (pintype "bidirectional"))
      (node (ref "U5") (pin "27") (pinfunction "MISO_27") (pintype "bidirectional"))
    )
    (net (code "24") (name "/DRV8323_MOSI") (class "Default")
      (node (ref "DRV_MOSI") (pin "P$1") (pinfunction "P$1_P$1") (pintype "bidirectional"))
      (node (ref "U1") (pin "15") (pinfunction "PA7_15") (pintype "bidirectional"))
      (node (ref "U5") (pin "28") (pinfunction "MOSI_28") (pintype "bidirectional"))
    )
    (net (code "25") (name "/DRV8323_SCLK") (class "Default")
      (node (ref "DRV_SCK") (pin "P$1") (pinfunction "P$1_P$1") (pintype "bidirectional"))
      (node (ref "U1") (pin "13") (pinfunction "PA5_13") (pintype "bidirectional"))
      (node (ref "U5") (pin "29") (pinfunction "SCLK_29") (pintype "bidirectional"))
    )
    (net (code "26") (name "/GHA") (class "Default")
      (node (ref "Q1") (pin "4") (pinfunction "G_4") (pintype "passive"))
      (node (ref "U5") (pin "6") (pinfunction "GHA_6") (pintype "bidirectional"))
    )
    (net (code "27") (name "/GHB") (class "Default")
      (node (ref "Q3") (pin "4") (pinfunction "G_4") (pintype "passive"))
      (node (ref "U5") (pin "15") (pinfunction "GHB_15") (pintype "bidirectional"))
    )
    (net (code "28") (name "/GHC") (class "Default")
      (node (ref "Q5") (pin "4") (pinfunction "G_4") (pintype "passive"))
      (node (ref "U5") (pin "16") (pinfunction "GHC_16") (pintype "bidirectional"))
    )
    (net (code "29") (name "/GLA") (class "Default")
      (node (ref "Q2") (pin "4") (pinfunction "G_4") (pintype "passive"))
      (node (ref "U5") (pin "8") (pinfunction "GLA_8") (pintype "bidirectional"))
    )
    (net (code "30") (name "/GLB") (class "Default")
      (node (ref "Q4") (pin "4") (pinfunction "G_4") (pintype "passive"))
      (node (ref "U5") (pin "13") (pinfunction "GLB_13") (pintype "bidirectional"))
    )
    (net (code "31") (name "/GLC") (class "Default")
      (node (ref "Q6") (pin "4") (pinfunction "G_4") (pintype "passive"))
      (node (ref "U5") (pin "18") (pinfunction "GLC_18") (pintype "bidirectional"))
    )
    (net (code "32") (name "/I2C_ABS_SCL") (class "Default")
      (node (ref "ABS") (pin "2") (pinfunction "2_2") (pintype "passive"))
      (node (ref "R4") (pin "P$2") (pinfunction "P$2_P$2") (pintype "passive"))
      (node (ref "U1") (pin "46") (pinfunction "PB8-BOOT0_46") (pintype "bidirectional"))
    )
    (net (code "33") (name "/I2C_ABS_SDA") (class "Default")
      (node (ref "ABS") (pin "3") (pinfunction "3_3") (pintype "passive"))
      (node (ref "R3") (pin "P$2") (pinfunction "P$2_P$2") (pintype "passive"))
      (node (ref "U1") (pin "47") (pinfunction "PB9_47") (pintype "bidirectional"))
    )
    (net (code "34") (name "/LED1") (class "Default")
      (node (ref "D3") (pin "CATHODE") (pinfunction "CATHODE_CATHODE") (pintype "power_in"))
      (node (ref "U1") (pin "5") (pinfunction "PF0-OSC_IN_5") (pintype "bidirectional"))
    )
    (net (code "35") (name "/LED2") (class "Default")
      (node (ref "D2") (pin "CATHODE") (pinfunction "CATHODE_CATHODE") (pintype "power_in"))
      (node (ref "U1") (pin "6") (pinfunction "PF1-OSC_OUT_6") (pintype "bidirectional"))
    )
    (net (code "36") (name "/MOTOR1") (class "Default")
      (node (ref "MOT1") (pin "P$1") (pinfunction "P$1_P$1") (pintype "bidirectional"))
      (node (ref "U1") (pin "8") (pinfunction "PA0_8") (pintype "bidirectional"))
      (node (ref "U5") (pin "32") (pinfunction "INHA_32") (pintype "bidirectional"))
    )
    (net (code "37") (name "/MOTOR2") (class "Default")
      (node (ref "MOT2") (pin "P$1") (pinfunction "P$1_P$1") (pintype "bidirectional"))
      (node (ref "U1") (pin "9") (pinfunction "PA1_9") (pintype "bidirectional"))
      (node (ref "U5") (pin "34") (pinfunction "INHB_34") (pintype "bidirectional"))
    )
    (net (code "38") (name "/MOTOR3") (class "Default")
      (node (ref "MOT3") (pin "P$1") (pinfunction "P$1_P$1") (pintype "bidirectional"))
      (node (ref "U1") (pin "10") (pinfunction "PA2_10") (pintype "bidirectional"))
      (node (ref "U5") (pin "36") (pinfunction "INHC_36") (pintype "bidirectional"))
    )
    (net (code "39") (name "/MOTOR_ENABLE") (class "Default")
      (node (ref "U1") (pin "11") (pinfunction "PA3_11") (pintype "bidirectional"))
      (node (ref "U5") (pin "31") (pinfunction "ENABLE_31") (pintype "bidirectional"))
    )
    (net (code "40") (name "/MOTOR_FAULT") (class "Default")
      (node (ref "R14") (pin "P$2") (pinfunction "P$2_P$2") (pintype "passive"))
      (node (ref "U1") (pin "44") (pinfunction "PB6_44") (pintype "bidirectional"))
      (node (ref "U5") (pin "26") (pinfunction "FAULT_26") (pintype "bidirectional"))
    )
    (net (code "41") (name "/MOTOR_HIZ") (class "Default")
      (node (ref "U1") (pin "45") (pinfunction "PB7_45") (pintype "bidirectional"))
      (node (ref "U5") (pin "33") (pinfunction "INLA_33") (pintype "bidirectional"))
      (node (ref "U5") (pin "35") (pinfunction "INLB_35") (pintype "bidirectional"))
      (node (ref "U5") (pin "37") (pinfunction "INLC_37") (pintype "bidirectional"))
    )
    (net (code "42") (name "/NRST") (class "Default")
      (node (ref "C3") (pin "P$1") (pinfunction "P$1_P$1") (pintype "passive"))
      (node (ref "SWD") (pin "2") (pinfunction "2_2") (pintype "passive"))
      (node (ref "U1") (pin "7") (pinfunction "PG10-NRST_7") (pintype "bidirectional"))
    )
    (net (code "43") (name "/SECONDARY_ENC_CS") (class "Default")
      (node (ref "ENC") (pin "2") (pinfunction "2_2") (pintype "passive"))
      (node (ref "U1") (pin "2") (pinfunction "PC13_2") (pintype "bidirectional"))
    )
    (net (code "44") (name "/SHA") (class "Default")
      (node (ref "A") (pin "1") (pinfunction "P$1_1") (pintype "bidirectional"))
      (node (ref "DA") (pin "P$1") (pinfunction "P$1_P$1") (pintype "bidirectional"))
      (node (ref "Q1") (pin "1") (pinfunction "S_1") (pintype "passive"))
      (node (ref "Q1") (pin "2") (pinfunction "S_2") (pintype "passive"))
      (node (ref "Q1") (pin "3") (pinfunction "S_3") (pintype "passive"))
      (node (ref "Q2") (pin "5") (pinfunction "D_5") (pintype "passive"))
      (node (ref "Q2") (pin "6") (pinfunction "D_6") (pintype "passive"))
      (node (ref "Q2") (pin "7") (pinfunction "D_7") (pintype "passive"))
      (node (ref "Q2") (pin "8") (pinfunction "D_8") (pintype "passive"))
      (node (ref "Q2") (pin "PAD") (pinfunction "D_PAD") (pintype "passive"))
      (node (ref "U5") (pin "7") (pinfunction "SHA_7") (pintype "bidirectional"))
    )
    (net (code "45") (name "/SHB") (class "Default")
      (node (ref "B") (pin "1") (pinfunction "P$1_1") (pintype "bidirectional"))
      (node (ref "DB") (pin "P$1") (pinfunction "P$1_P$1") (pintype "bidirectional"))
      (node (ref "Q3") (pin "1") (pinfunction "S_1") (pintype "passive"))
      (node (ref "Q3") (pin "2") (pinfunction "S_2") (pintype "passive"))
      (node (ref "Q3") (pin "3") (pinfunction "S_3") (pintype "passive"))
      (node (ref "Q4") (pin "5") (pinfunction "D_5") (pintype "passive"))
      (node (ref "Q4") (pin "6") (pinfunction "D_6") (pintype "passive"))
      (node (ref "Q4") (pin "7") (pinfunction "D_7") (pintype "passive"))
      (node (ref "Q4") (pin "8") (pinfunction "D_8") (pintype "passive"))
      (node (ref "Q4") (pin "PAD") (pinfunction "D_PAD") (pintype "passive"))
      (node (ref "U5") (pin "14") (pinfunction "SHB_14") (pintype "bidirectional"))
    )
    (net (code "46") (name "/SHC") (class "Default")
      (node (ref "C") (pin "1") (pinfunction "P$1_1") (pintype "bidirectional"))
      (node (ref "DC") (pin "P$1") (pinfunction "P$1_P$1") (pintype "bidirectional"))
      (node (ref "Q5") (pin "1") (pinfunction "S_1") (pintype "passive"))
      (node (ref "Q5") (pin "2") (pinfunction "S_2") (pintype "passive"))
      (node (ref "Q5") (pin "3") (pinfunction "S_3") (pintype "passive"))
      (node (ref "Q6") (pin "5") (pinfunction "D_5") (pintype "passive"))
      (node (ref "Q6") (pin "6") (pinfunction "D_6") (pintype "passive"))
      (node (ref "Q6") (pin "7") (pinfunction "D_7") (pintype "passive"))
      (node (ref "Q6") (pin "8") (pinfunction "D_8") (pintype "passive"))
      (node (ref "Q6") (pin "PAD") (pinfunction "D_PAD") (pintype "passive"))
      (node (ref "U5") (pin "17") (pinfunction "SHC_17") (pintype "bidirectional"))
    )
    (net (code "47") (name "/SWCLK") (class "Default")
      (node (ref "SWD") (pin "5") (pinfunction "5_5") (pintype "passive"))
      (node (ref "U1") (pin "37") (pinfunction "PA14_37") (pintype "bidirectional"))
    )
    (net (code "48") (name "/SWDIO") (class "Default")
      (node (ref "SWD") (pin "3") (pinfunction "3_3") (pintype "passive"))
      (node (ref "U1") (pin "36") (pinfunction "PA13_36") (pintype "bidirectional"))
    )
    (net (code "49") (name "/SXA_N") (class "Default")
      (node (ref "SH1") (pin "1") (pinfunction "P$1_1") (pintype "bidirectional"))
      (node (ref "U5") (pin "10") (pinfunction "SNA_10") (pintype "bidirectional"))
    )
    (net (code "50") (name "/SXA_P") (class "Default")
      (node (ref "Q2") (pin "1") (pinfunction "S_1") (pintype "passive"))
      (node (ref "Q2") (pin "2") (pinfunction "S_2") (pintype "passive"))
      (node (ref "Q2") (pin "3") (pinfunction "S_3") (pintype "passive"))
      (node (ref "RA") (pin "2") (pinfunction "2_2") (pintype "passive"))
      (node (ref "U5") (pin "9") (pinfunction "SPA_9") (pintype "bidirectional"))
    )
    (net (code "51") (name "/SXB_N") (class "Default")
      (node (ref "SH2") (pin "1") (pinfunction "P$1_1") (pintype "bidirectional"))
      (node (ref "U5") (pin "11") (pinfunction "SNB_11") (pintype "bidirectional"))
    )
    (net (code "52") (name "/SXB_P") (class "Default")
      (node (ref "Q4") (pin "1") (pinfunction "S_1") (pintype "passive"))
      (node (ref "Q4") (pin "2") (pinfunction "S_2") (pintype "passive"))
      (node (ref "Q4") (pin "3") (pinfunction "S_3") (pintype "passive"))
      (node (ref "RB") (pin "2") (pinfunction "2_2") (pintype "passive"))
      (node (ref "U5") (pin "12") (pinfunction "SPB_12") (pintype "bidirectional"))
    )
    (net (code "53") (name "/SXC_N") (class "Default")
      (node (ref "SH3") (pin "1") (pinfunction "P$1_1") (pintype "bidirectional"))
      (node (ref "U5") (pin "20") (pinfunction "SNC_20") (pintype "bidirectional"))
    )
    (net (code "54") (name "/SXC_P") (class "Default")
      (node (ref "Q6") (pin "1") (pinfunction "S_1") (pintype "passive"))
      (node (ref "Q6") (pin "2") (pinfunction "S_2") (pintype "passive"))
      (node (ref "Q6") (pin "3") (pinfunction "S_3") (pintype "passive"))
      (node (ref "RC") (pin "2") (pinfunction "2_2") (pintype "passive"))
      (node (ref "U5") (pin "19") (pinfunction "SPC_19") (pintype "bidirectional"))
    )
    (net (code "55") (name "/VBAT_SENSE") (class "Default")
      (node (ref "C57") (pin "P$1") (pinfunction "P$1_P$1") (pintype "passive"))
      (node (ref "R5") (pin "P$1") (pinfunction "P$1_P$1") (pintype "passive"))
      (node (ref "R6") (pin "P$2") (pinfunction "P$2_P$2") (pintype "passive"))
      (node (ref "U1") (pin "25") (pinfunction "PB12_25") (pintype "bidirectional"))
    )
    (net (code "56") (name "/VSW") (class "Default")
      (node (ref "L1") (pin "2") (pinfunction "2_2") (pintype "passive"))
      (node (ref "U4") (pin "8") (pinfunction "LX_8") (pintype "passive"))
    )
    (net (code "57") (name "/VTEMP_FET") (class "Default")
      (node (ref "C13") (pin "P$1") (pinfunction "P$1_P$1") (pintype "passive"))
      (node (ref "R8") (pin "P$2") (pinfunction "P$2_P$2") (pintype "passive"))
      (node (ref "R9") (pin "P$1") (pinfunction "P$1_P$1") (pintype "passive"))
      (node (ref "U1") (pin "31") (pinfunction "PA9_31") (pintype "bidirectional"))
    )
    (net (code "58") (name "/VTEMP_MOT") (class "Default")
      (node (ref "R7") (pin "P$1") (pinfunction "P$1_P$1") (pintype "passive"))
      (node (ref "TEMP2") (pin "P$1") (pinfunction "P$1_P$1") (pintype "bidirectional"))
      (node (ref "U1") (pin "30") (pinfunction "PA8_30") (pintype "bidirectional"))
    )
    (net (code "59") (name "GND") (class "Default")
      (node (ref "ABS") (pin "4") (pinfunction "4_4") (pintype "passive"))
      (node (ref "C1") (pin "P$2") (pinfunction "P$2_P$2") (pintype "passive"))
      (node (ref "C10") (pin "P$2") (pinfunction "P$2_P$2") (pintype "passive"))
      (node (ref "C11") (pin "P$2") (pinfunction "P$2_P$2") (pintype "passive"))
      (node (ref "C12") (pin "P$2") (pinfunction "P$2_P$2") (pintype "passive"))
      (node (ref "C13") (pin "P$2") (pinfunction "P$2_P$2") (pintype "passive"))
      (node (ref "C18") (pin "P$1") (pinfunction "P$1_P$1") (pintype "passive"))
      (node (ref "C2") (pin "P$2") (pinfunction "P$2_P$2") (pintype "passive"))
      (node (ref "C20") (pin "P$2") (pinfunction "P$2_P$2") (pintype "passive"))
      (node (ref "C21") (pin "P$2") (pinfunction "P$2_P$2") (pintype "passive"))
      (node (ref "C3") (pin "P$2") (pinfunction "P$2_P$2") (pintype "passive"))
      (node (ref "C4") (pin "P$2") (pinfunction "P$2_P$2") (pintype "passive"))
      (node (ref "C5") (pin "P$2") (pinfunction "P$2_P$2") (pintype "passive"))
      (node (ref "C56") (pin "P$2") (pinfunction "P$2_P$2") (pintype "passive"))
      (node (ref "C57") (pin "P$2") (pinfunction "P$2_P$2") (pintype "passive"))
      (node (ref "C6") (pin "P$2") (pinfunction "P$2_P$2") (pintype "passive"))
      (node (ref "C7") (pin "P$1") (pinfunction "P$1_P$1") (pintype "passive"))
      (node (ref "C8") (pin "P$2") (pinfunction "P$2_P$2") (pintype "passive"))
      (node (ref "C9") (pin "P$2") (pinfunction "P$2_P$2") (pintype "passive"))
      (node (ref "CAN1") (pin "3") (pinfunction "3_3") (pintype "passive"))
      (node (ref "CAN2") (pin "3") (pinfunction "3_3") (pintype "passive"))
      (node (ref "D4") (pin "3") (pinfunction "3_3") (pintype "bidirectional"))
      (node (ref "DG1") (pin "P$1") (pinfunction "P$1_P$1") (pintype "bidirectional"))
      (node (ref "DG2") (pin "P$1") (pinfunction "P$1_P$1") (pintype "bidirectional"))
      (node (ref "ENC") (pin "3") (pinfunction "3_3") (pintype "passive"))
      (node (ref "R6") (pin "P$1") (pinfunction "P$1_P$1") (pintype "passive"))
      (node (ref "R7") (pin "P$2") (pinfunction "P$2_P$2") (pintype "passive"))
      (node (ref "R9") (pin "P$2") (pinfunction "P$2_P$2") (pintype "passive"))
      (node (ref "SH4") (pin "2") (pinfunction "P$2_2") (pintype "bidirectional"))
      (node (ref "SWD") (pin "4") (pinfunction "4_4") (pintype "passive"))
      (node (ref "U1") (pin "29") (pinfunction "PC6_29") (pintype "bidirectional"))
      (node (ref "U1") (pin "38") (pinfunction "PA15_38") (pintype "bidirectional"))
      (node (ref "U1") (pin "49") (pinfunction "THERMALPAD_49") (pintype "bidirectional"))
      (node (ref "U2") (pin "2") (pinfunction "GND_2") (pintype "power_in"))
      (node (ref "U2") (pin "5") (pinfunction "SHDN_5") (pintype "input"))
      (node (ref "U2") (pin "8") (pinfunction "STB_8") (pintype "input"))
      (node (ref "U3") (pin "13") (pinfunction "GND_13") (pintype "bidirectional"))
      (node (ref "U3") (pin "5") (pinfunction "TEST_5") (pintype "bidirectional"))
      (node (ref "U4") (pin "7") (pinfunction "GND_7") (pintype "power_in"))
      (node (ref "U5") (pin "25") (pinfunction "AGND_25") (pintype "bidirectional"))
    )
    (net (code "60") (name "Net-(C55-PadP$1)") (class "Default")
      (node (ref "C55") (pin "P$1") (pinfunction "P$1_P$1") (pintype "passive"))
      (node (ref "M3") (pin "P$1") (pinfunction "P$1_P$1") (pintype "bidirectional"))
      (node (ref "R10") (pin "P$1") (pinfunction "P$1_P$1") (pintype "passive"))
    )
    (net (code "61") (name "Net-(D2-PadANODE)") (class "Default")
      (node (ref "D2") (pin "ANODE") (pinfunction "ANODE_ANODE") (pintype "power_in"))
      (node (ref "R2") (pin "P$2") (pinfunction "P$2_P$2") (pintype "passive"))
    )
    (net (code "62") (name "Net-(D3-PadANODE)") (class "Default")
      (node (ref "D3") (pin "ANODE") (pinfunction "ANODE_ANODE") (pintype "power_in"))
      (node (ref "R1") (pin "P$2") (pinfunction "P$2_P$2") (pintype "passive"))
    )
    (net (code "63") (name "Net-(U4-VCC)") (class "Default")
      (node (ref "C20") (pin "P$1") (pinfunction "P$1_P$1") (pintype "passive"))
      (node (ref "U4") (pin "3") (pinfunction "VCC_3") (pintype "power_in"))
    )
    (net (code "64") (name "Net-(U5-CPH)") (class "Default")
      (node (ref "C16") (pin "P$1") (pinfunction "P$1_P$1") (pintype "passive"))
      (node (ref "U5") (pin "2") (pinfunction "CPH_2") (pintype "bidirectional"))
    )
    (net (code "65") (name "Net-(U5-CPL)") (class "Default")
      (node (ref "C16") (pin "P$2") (pinfunction "P$2_P$2") (pintype "passive"))
      (node (ref "U5") (pin "1") (pinfunction "CPL_1") (pintype "bidirectional"))
    )
    (net (code "66") (name "Net-(U5-DVDD)") (class "Default")
      (node (ref "C17") (pin "P$2") (pinfunction "P$2_P$2") (pintype "passive"))
      (node (ref "U5") (pin "38") (pinfunction "DVDD_38") (pintype "bidirectional"))
    )
    (net (code "67") (name "Net-(U5-VCP)") (class "Default")
      (node (ref "C15") (pin "P$2") (pinfunction "P$2_P$2") (pintype "passive"))
      (node (ref "U5") (pin "5") (pinfunction "VCP_5") (pintype "bidirectional"))
    )
    (net (code "68") (name "Net-(U5-VGLS)") (class "Default")
      (node (ref "C38") (pin "P$2") (pinfunction "P$2_P$2") (pintype "passive"))
      (node (ref "U5") (pin "40") (pinfunction "VGLS_40") (pintype "bidirectional"))
    )
    (net (code "69") (name "V+") (class "Default")
      (node (ref "C14") (pin "P$1") (pinfunction "P$1_P$1") (pintype "passive"))
      (node (ref "C15") (pin "P$1") (pinfunction "P$1_P$1") (pintype "passive"))
      (node (ref "C19") (pin "P$1") (pinfunction "P$1_P$1") (pintype "passive"))
      (node (ref "C22") (pin "P$1") (pinfunction "P$1_P$1") (pintype "passive"))
      (node (ref "C23") (pin "P$1") (pinfunction "P$1_P$1") (pintype "passive"))
      (node (ref "C24") (pin "P$1") (pinfunction "P$1_P$1") (pintype "passive"))
      (node (ref "C25") (pin "P$1") (pinfunction "P$1_P$1") (pintype "passive"))
      (node (ref "C26") (pin "P$1") (pinfunction "P$1_P$1") (pintype "passive"))
      (node (ref "C27") (pin "P$1") (pinfunction "P$1_P$1") (pintype "passive"))
      (node (ref "C28") (pin "P$1") (pinfunction "P$1_P$1") (pintype "passive"))
      (node (ref "C29") (pin "P$1") (pinfunction "P$1_P$1") (pintype "passive"))
      (node (ref "C30") (pin "P$1") (pinfunction "P$1_P$1") (pintype "passive"))
      (node (ref "C31") (pin "P$1") (pinfunction "P$1_P$1") (pintype "passive"))
      (node (ref "C32") (pin "P$1") (pinfunction "P$1_P$1") (pintype "passive"))
      (node (ref "C33") (pin "P$1") (pinfunction "P$1_P$1") (pintype "passive"))
      (node (ref "C34") (pin "P$1") (pinfunction "P$1_P$1") (pintype "passive"))
      (node (ref "C35") (pin "P$1") (pinfunction "P$1_P$1") (pintype "passive"))
      (node (ref "C36") (pin "P$1") (pinfunction "P$1_P$1") (pintype "passive"))
      (node (ref "C37") (pin "P$1") (pinfunction "P$1_P$1") (pintype "passive"))
      (node (ref "C39") (pin "P$1") (pinfunction "P$1_P$1") (pintype "passive"))
      (node (ref "C40") (pin "P$1") (pinfunction "P$1_P$1") (pintype "passive"))
      (node (ref "C41") (pin "P$1") (pinfunction "P$1_P$1") (pintype "passive"))
      (node (ref "C42") (pin "P$1") (pinfunction "P$1_P$1") (pintype "passive"))
      (node (ref "C43") (pin "P$1") (pinfunction "P$1_P$1") (pintype "passive"))
      (node (ref "C44") (pin "P$1") (pinfunction "P$1_P$1") (pintype "passive"))
      (node (ref "C45") (pin "P$1") (pinfunction "P$1_P$1") (pintype "passive"))
      (node (ref "C46") (pin "P$1") (pinfunction "P$1_P$1") (pintype "passive"))
      (node (ref "C47") (pin "P$1") (pinfunction "P$1_P$1") (pintype "passive"))
      (node (ref "C48") (pin "P$1") (pinfunction "P$1_P$1") (pintype "passive"))
      (node (ref "C49") (pin "P$1") (pinfunction "P$1_P$1") (pintype "passive"))
      (node (ref "C50") (pin "P$1") (pinfunction "P$1_P$1") (pintype "passive"))
      (node (ref "C51") (pin "P$1") (pinfunction "P$1_P$1") (pintype "passive"))
      (node (ref "C52") (pin "P$1") (pinfunction "P$1_P$1") (pintype "passive"))
      (node (ref "C53") (pin "P$1") (pinfunction "P$1_P$1") (pintype "passive"))
      (node (ref "C54") (pin "P$1") (pinfunction "P$1_P$1") (pintype "passive"))
      (node (ref "J1") (pin "1") (pinfunction "1_1") (pintype "passive"))
      (node (ref "J2") (pin "1") (pinfunction "1_1") (pintype "passive"))
      (node (ref "Q1") (pin "5") (pinfunction "D_5") (pintype "passive"))
      (node (ref "Q1") (pin "6") (pinfunction "D_6") (pintype "passive"))
      (node (ref "Q1") (pin "7") (pinfunction "D_7") (pintype "passive"))
      (node (ref "Q1") (pin "8") (pinfunction "D_8") (pintype "passive"))
      (node (ref "Q1") (pin "PAD") (pinfunction "D_PAD") (pintype "passive"))
      (node (ref "Q3") (pin "5") (pinfunction "D_5") (pintype "passive"))
      (node (ref "Q3") (pin "6") (pinfunction "D_6") (pintype "passive"))
      (node (ref "Q3") (pin "7") (pinfunction "D_7") (pintype "passive"))
      (node (ref "Q3") (pin "8") (pinfunction "D_8") (pintype "passive"))
      (node (ref "Q3") (pin "PAD") (pinfunction "D_PAD") (pintype "passive"))
      (node (ref "Q5") (pin "5") (pinfunction "D_5") (pintype "passive"))
      (node (ref "Q5") (pin "6") (pinfunction "D_6") (pintype "passive"))
      (node (ref "Q5") (pin "7") (pinfunction "D_7") (pintype "passive"))
      (node (ref "Q5") (pin "8") (pinfunction "D_8") (pintype "passive"))
      (node (ref "Q5") (pin "PAD") (pinfunction "D_PAD") (pintype "passive"))
      (node (ref "R5") (pin "P$2") (pinfunction "P$2_P$2") (pintype "passive"))
      (node (ref "U4") (pin "1") (pinfunction "VIN_1") (pintype "input"))
      (node (ref "U4") (pin "2") (pinfunction "EN/UVLO_2") (pintype "input"))
      (node (ref "U5") (pin "3") (pinfunction "VM_3") (pintype "bidirectional"))
      (node (ref "U5") (pin "4") (pinfunction "VDRAIN_4") (pintype "bidirectional"))
    )
    (net (code "70") (name "V-") (class "Default")
      (node (ref "C14") (pin "P$2") (pinfunction "P$2_P$2") (pintype "passive"))
      (node (ref "C17") (pin "P$1") (pinfunction "P$1_P$1") (pintype "passive"))
      (node (ref "C19") (pin "P$2") (pinfunction "P$2_P$2") (pintype "passive"))
      (node (ref "C22") (pin "P$2") (pinfunction "P$2_P$2") (pintype "passive"))
      (node (ref "C23") (pin "P$2") (pinfunction "P$2_P$2") (pintype "passive"))
      (node (ref "C24") (pin "P$2") (pinfunction "P$2_P$2") (pintype "passive"))
      (node (ref "C25") (pin "P$2") (pinfunction "P$2_P$2") (pintype "passive"))
      (node (ref "C26") (pin "P$2") (pinfunction "P$2_P$2") (pintype "passive"))
      (node (ref "C27") (pin "P$2") (pinfunction "P$2_P$2") (pintype "passive"))
      (node (ref "C28") (pin "P$2") (pinfunction "P$2_P$2") (pintype "passive"))
      (node (ref "C29") (pin "P$2") (pinfunction "P$2_P$2") (pintype "passive"))
      (node (ref "C30") (pin "P$2") (pinfunction "P$2_P$2") (pintype "passive"))
      (node (ref "C31") (pin "P$2") (pinfunction "P$2_P$2") (pintype "passive"))
      (node (ref "C32") (pin "P$2") (pinfunction "P$2_P$2") (pintype "passive"))
      (node (ref "C33") (pin "P$2") (pinfunction "P$2_P$2") (pintype "passive"))
      (node (ref "C34") (pin "P$2") (pinfunction "P$2_P$2") (pintype "passive"))
      (node (ref "C35") (pin "P$2") (pinfunction "P$2_P$2") (pintype "passive"))
      (node (ref "C36") (pin "P$2") (pinfunction "P$2_P$2") (pintype "passive"))
      (node (ref "C37") (pin "P$2") (pinfunction "P$2_P$2") (pintype "passive"))
      (node (ref "C38") (pin "P$1") (pinfunction "P$1_P$1") (pintype "passive"))
      (node (ref "C39") (pin "P$2") (pinfunction "P$2_P$2") (pintype "passive"))
      (node (ref "C40") (pin "P$2") (pinfunction "P$2_P$2") (pintype "passive"))
      (node (ref "C41") (pin "P$2") (pinfunction "P$2_P$2") (pintype "passive"))
      (node (ref "C42") (pin "P$2") (pinfunction "P$2_P$2") (pintype "passive"))
      (node (ref "C43") (pin "P$2") (pinfunction "P$2_P$2") (pintype "passive"))
      (node (ref "C44") (pin "P$2") (pinfunction "P$2_P$2") (pintype "passive"))
      (node (ref "C45") (pin "P$2") (pinfunction "P$2_P$2") (pintype "passive"))
      (node (ref "C46") (pin "P$2") (pinfunction "P$2_P$2") (pintype "passive"))
      (node (ref "C47") (pin "P$2") (pinfunction "P$2_P$2") (pintype "passive"))
      (node (ref "C48") (pin "P$2") (pinfunction "P$2_P$2") (pintype "passive"))
      (node (ref "C49") (pin "P$2") (pinfunction "P$2_P$2") (pintype "passive"))
      (node (ref "C50") (pin "P$2") (pinfunction "P$2_P$2") (pintype "passive"))
      (node (ref "C51") (pin "P$2") (pinfunction "P$2_P$2") (pintype "passive"))
      (node (ref "C52") (pin "P$2") (pinfunction "P$2_P$2") (pintype "passive"))
      (node (ref "C53") (pin "P$2") (pinfunction "P$2_P$2") (pintype "passive"))
      (node (ref "C54") (pin "P$2") (pinfunction "P$2_P$2") (pintype "passive"))
      (node (ref "C55") (pin "P$2") (pinfunction "P$2_P$2") (pintype "passive"))
      (node (ref "J1") (pin "2") (pinfunction "2_2") (pintype "passive"))
      (node (ref "J2") (pin "2") (pinfunction "2_2") (pintype "passive"))
      (node (ref "R10") (pin "P$2") (pinfunction "P$2_P$2") (pintype "passive"))
      (node (ref "RA") (pin "1") (pinfunction "1_1") (pintype "passive"))
      (node (ref "RB") (pin "1") (pinfunction "1_1") (pintype "passive"))
      (node (ref "RC") (pin "1") (pinfunction "1_1") (pintype "passive"))
      (node (ref "SH1") (pin "2") (pinfunction "P$2_2") (pintype "bidirectional"))
      (node (ref "SH2") (pin "2") (pinfunction "P$2_2") (pintype "bidirectional"))
      (node (ref "SH3") (pin "2") (pinfunction "P$2_2") (pintype "bidirectional"))
      (node (ref "SH4") (pin "1") (pinfunction "P$1_1") (pintype "bidirectional"))
      (node (ref "U5") (pin "39") (pinfunction "GND_39") (pintype "bidirectional"))
      (node (ref "U5") (pin "P1") (pinfunction "PAD_P1") (pintype "bidirectional"))
      (node (ref "U5") (pin "P12") (pinfunction "PAD_P12") (pintype "bidirectional"))
      (node (ref "U5") (pin "P13") (pinfunction "PAD_P13") (pintype "bidirectional"))
      (node (ref "U5") (pin "P14") (pinfunction "PAD_P14") (pintype "bidirectional"))
      (node (ref "U5") (pin "P17") (pinfunction "PAD_P17") (pintype "bidirectional"))
      (node (ref "U5") (pin "P18") (pinfunction "PAD_P18") (pintype "bidirectional"))
      (node (ref "U5") (pin "P19") (pinfunction "PAD_P19") (pintype "bidirectional"))
      (node (ref "U5") (pin "P2") (pinfunction "PAD_P2") (pintype "bidirectional"))
      (node (ref "U5") (pin "P3") (pinfunction "PAD_P3") (pintype "bidirectional"))
      (node (ref "U5") (pin "P7") (pinfunction "PAD_P7") (pintype "bidirectional"))
      (node (ref "U5") (pin "P8") (pinfunction "PAD_P8") (pintype "bidirectional"))
      (node (ref "U5") (pin "P9") (pinfunction "PAD_P9") (pintype "bidirectional"))
      (node (ref "U5") (pin "PAD") (pinfunction "PAD_PAD") (pintype "bidirectional"))
    )
    (net (code "71") (name "unconnected-(M1-PadP$1)") (class "Default")
      (node (ref "M1") (pin "P$1") (pinfunction "P$1_P$1") (pintype "bidirectional"))
    )
    (net (code "72") (name "unconnected-(M2-PadP$1)") (class "Default")
      (node (ref "M2") (pin "P$1") (pinfunction "P$1_P$1") (pintype "bidirectional"))
    )
    (net (code "73") (name "unconnected-(M4-PadP$1)") (class "Default")
      (node (ref "M4") (pin "P$1") (pinfunction "P$1_P$1") (pintype "bidirectional"))
    )
    (net (code "74") (name "unconnected-(SWD-Pad1)") (class "Default")
      (node (ref "SWD") (pin "1") (pinfunction "1_1") (pintype "passive"))
    )
    (net (code "75") (name "unconnected-(U1-PA10-Pad32)") (class "Default")
      (node (ref "U1") (pin "32") (pinfunction "PA10_32") (pintype "bidirectional"))
    )
    (net (code "76") (name "unconnected-(U1-PB3-Pad41)") (class "Default")
      (node (ref "U1") (pin "41") (pinfunction "PB3_41") (pintype "bidirectional"))
    )
    (net (code "77") (name "unconnected-(U1-PB10-Pad22)") (class "Default")
      (node (ref "U1") (pin "22") (pinfunction "PB10_22") (pintype "bidirectional"))
    )
    (net (code "78") (name "unconnected-(U3-I-Pad14)") (class "Default")
      (node (ref "U3") (pin "14") (pinfunction "I_14") (pintype "bidirectional"))
    )
    (net (code "79") (name "unconnected-(U3-PWM-Pad8)") (class "Default")
      (node (ref "U3") (pin "8") (pinfunction "PWM_8") (pintype "bidirectional"))
    )
    (net (code "80") (name "unconnected-(U3-VDD5V-Pad11)") (class "Default")
      (node (ref "U3") (pin "11") (pinfunction "VDD5V_11") (pintype "bidirectional"))
    )
    (net (code "81") (name "unconnected-(U4-MODE-Pad5)") (class "Default")
      (node (ref "U4") (pin "5") (pinfunction "MODE_5") (pintype "input"))
    )
    (net (code "82") (name "unconnected-(U4-~{RESET}-Pad6)") (class "Default")
      (node (ref "U4") (pin "6") (pinfunction "~{RESET}_6") (pintype "output"))
    )
  )
)
